# anookum_main.net
KiCad netlist of a schematic drawn in EAGLE
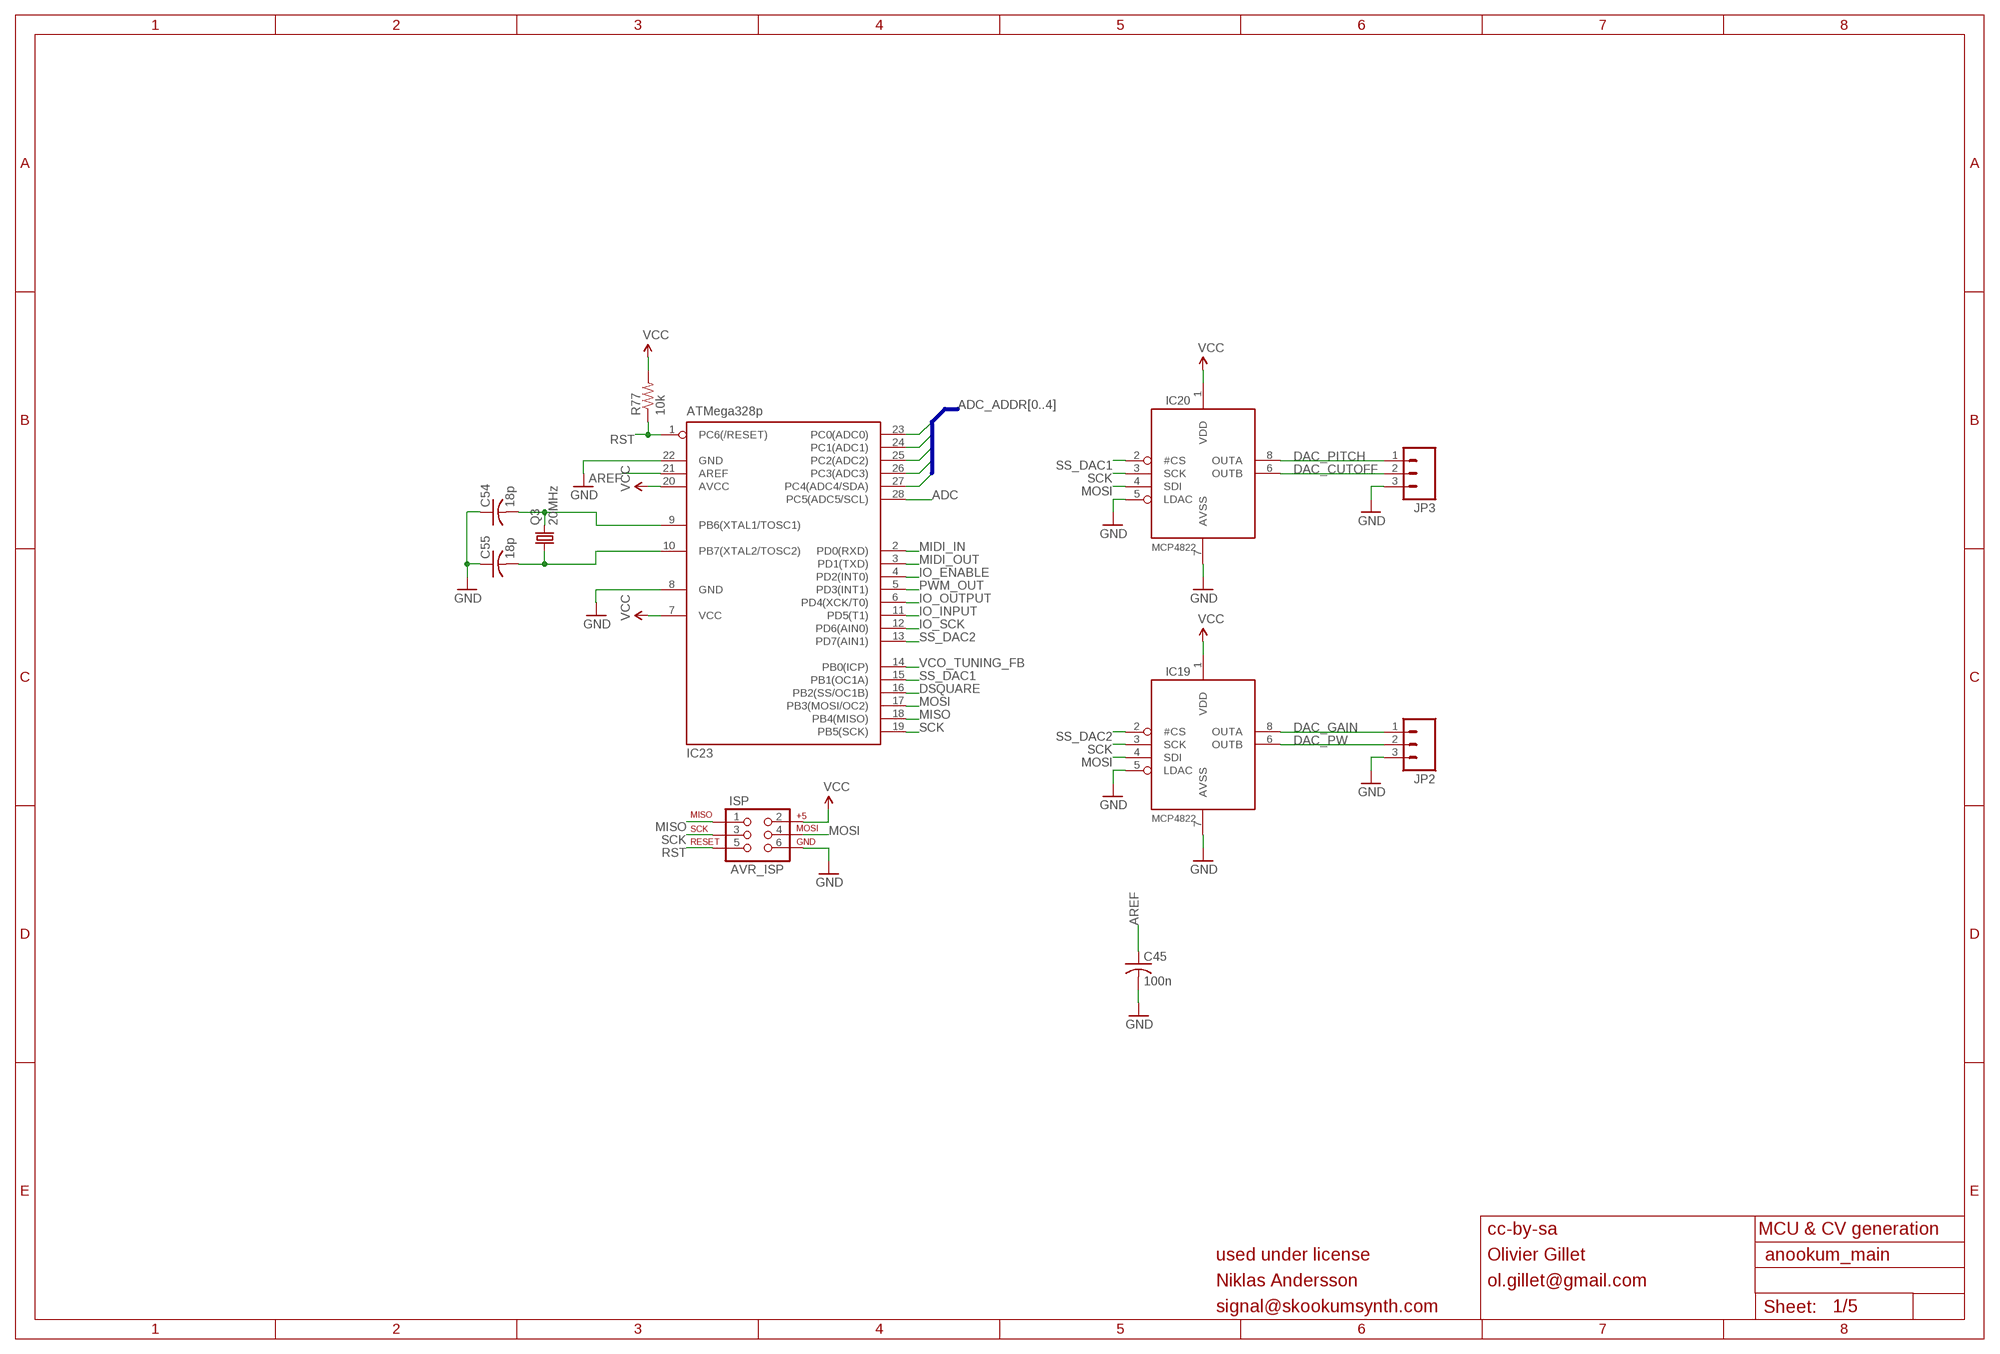
[diagram p0: schematic, sheet 1]
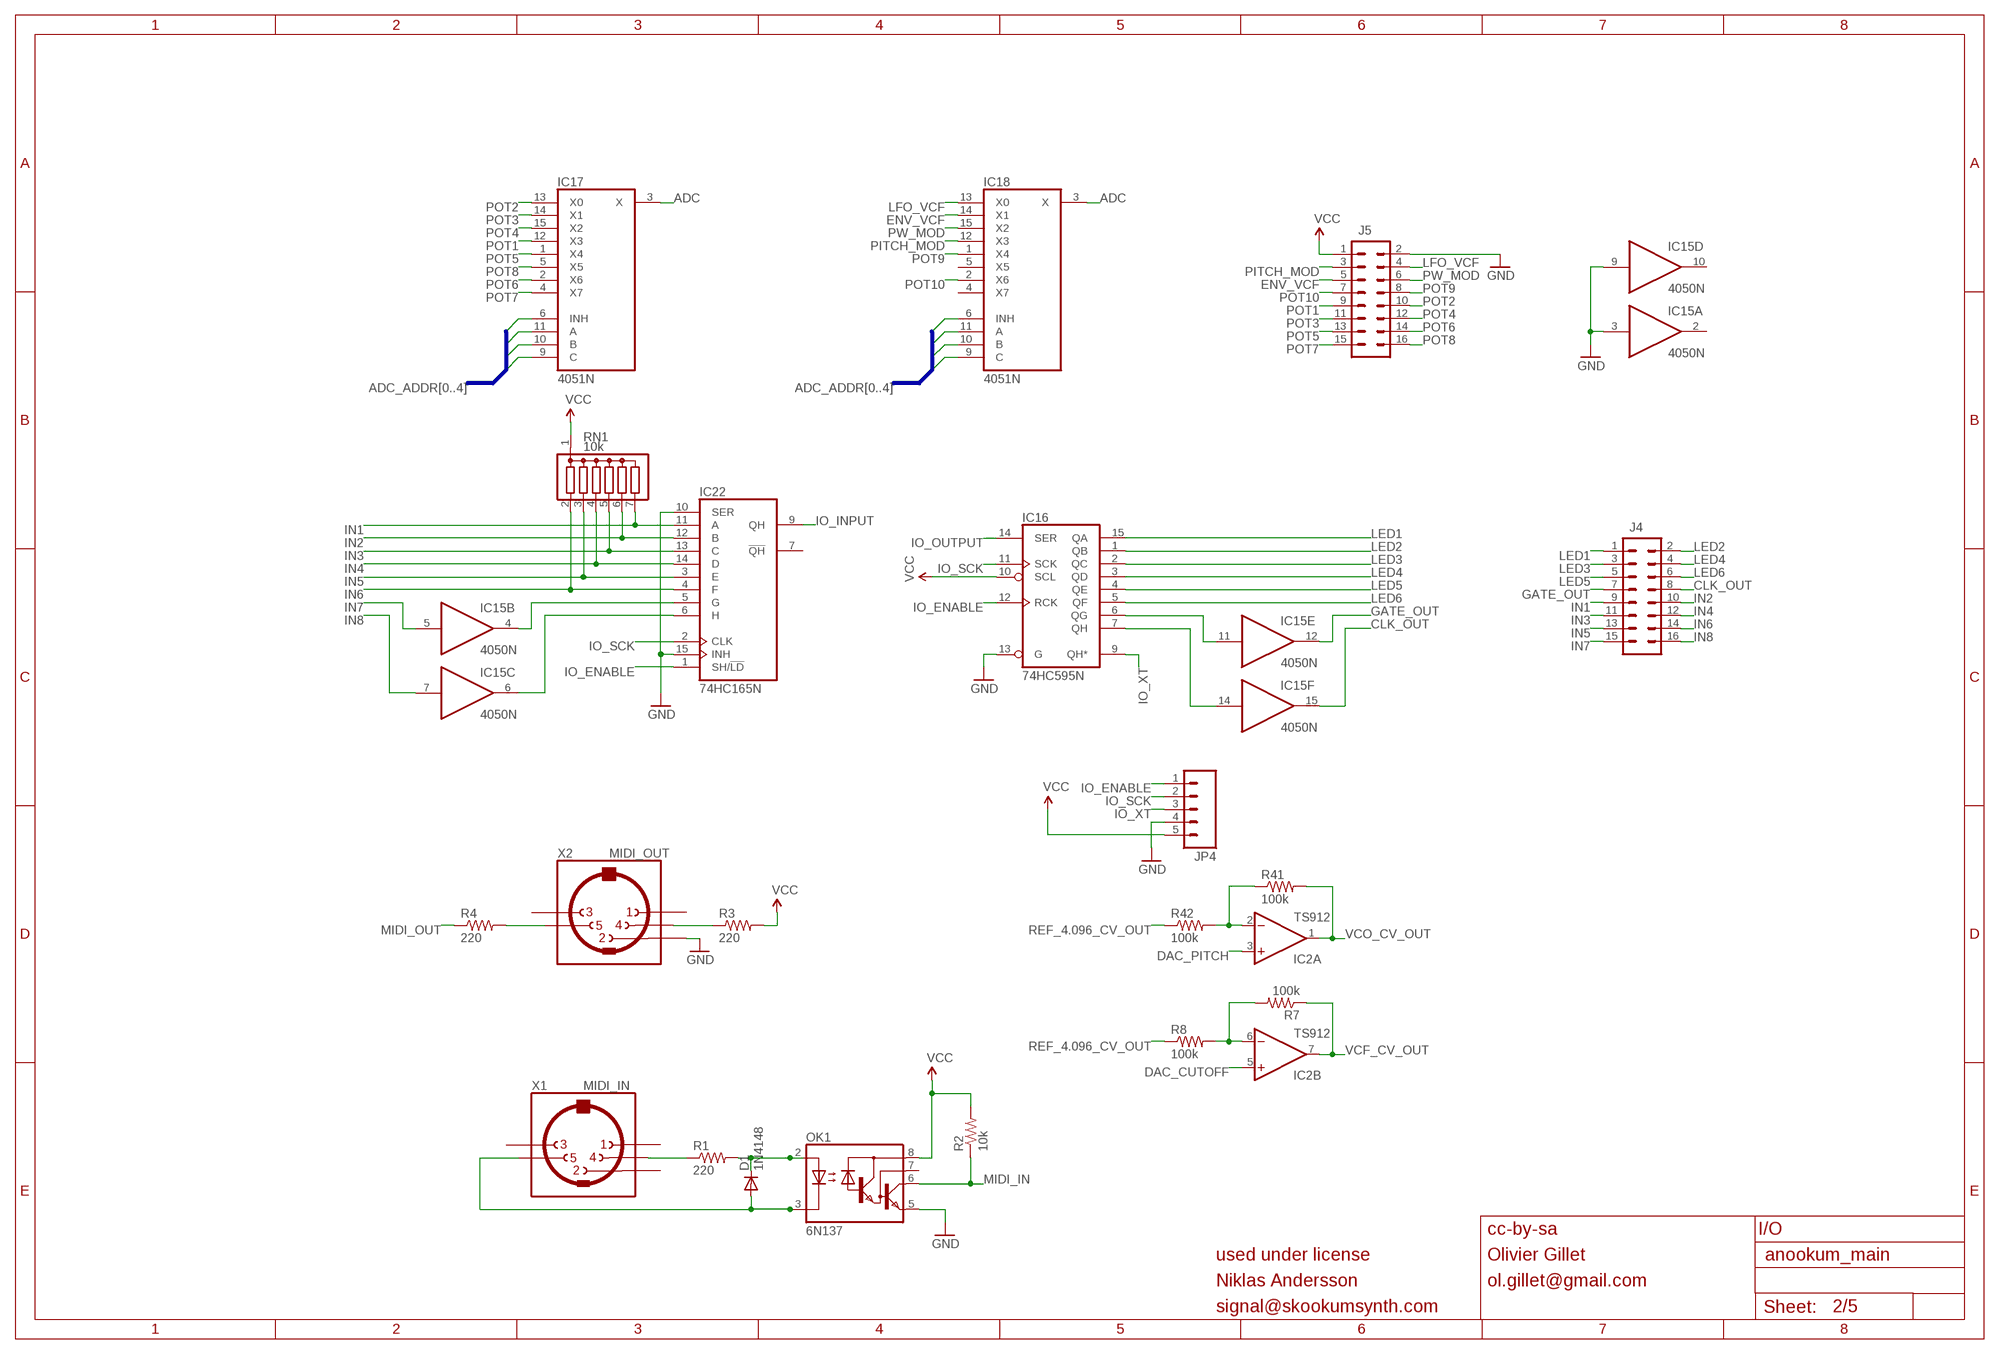
[diagram p1: schematic, sheet 2]
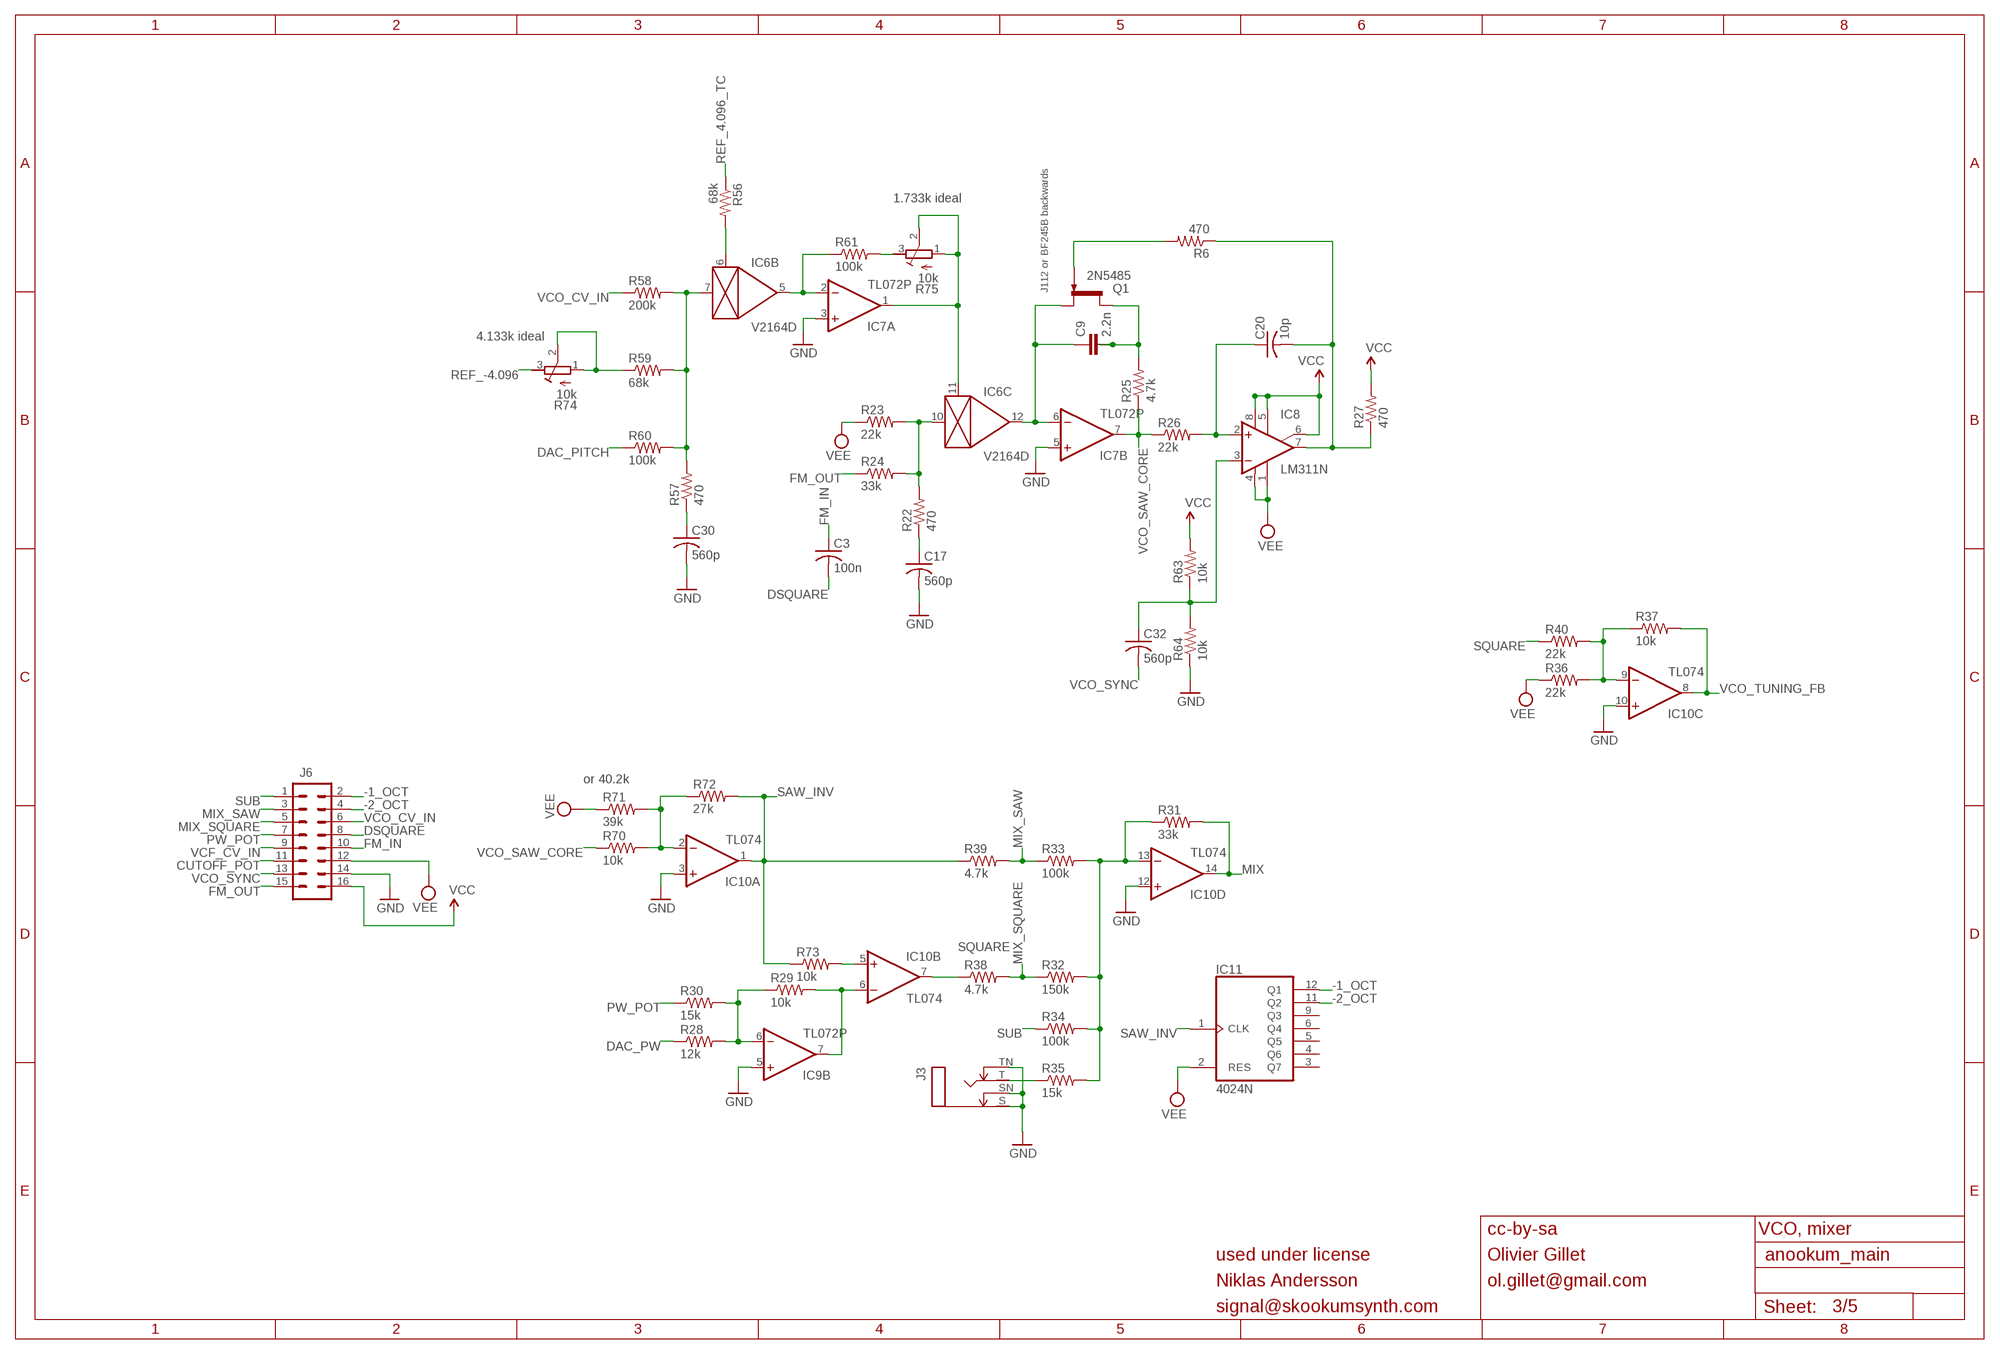
[diagram p2: schematic, sheet 3]
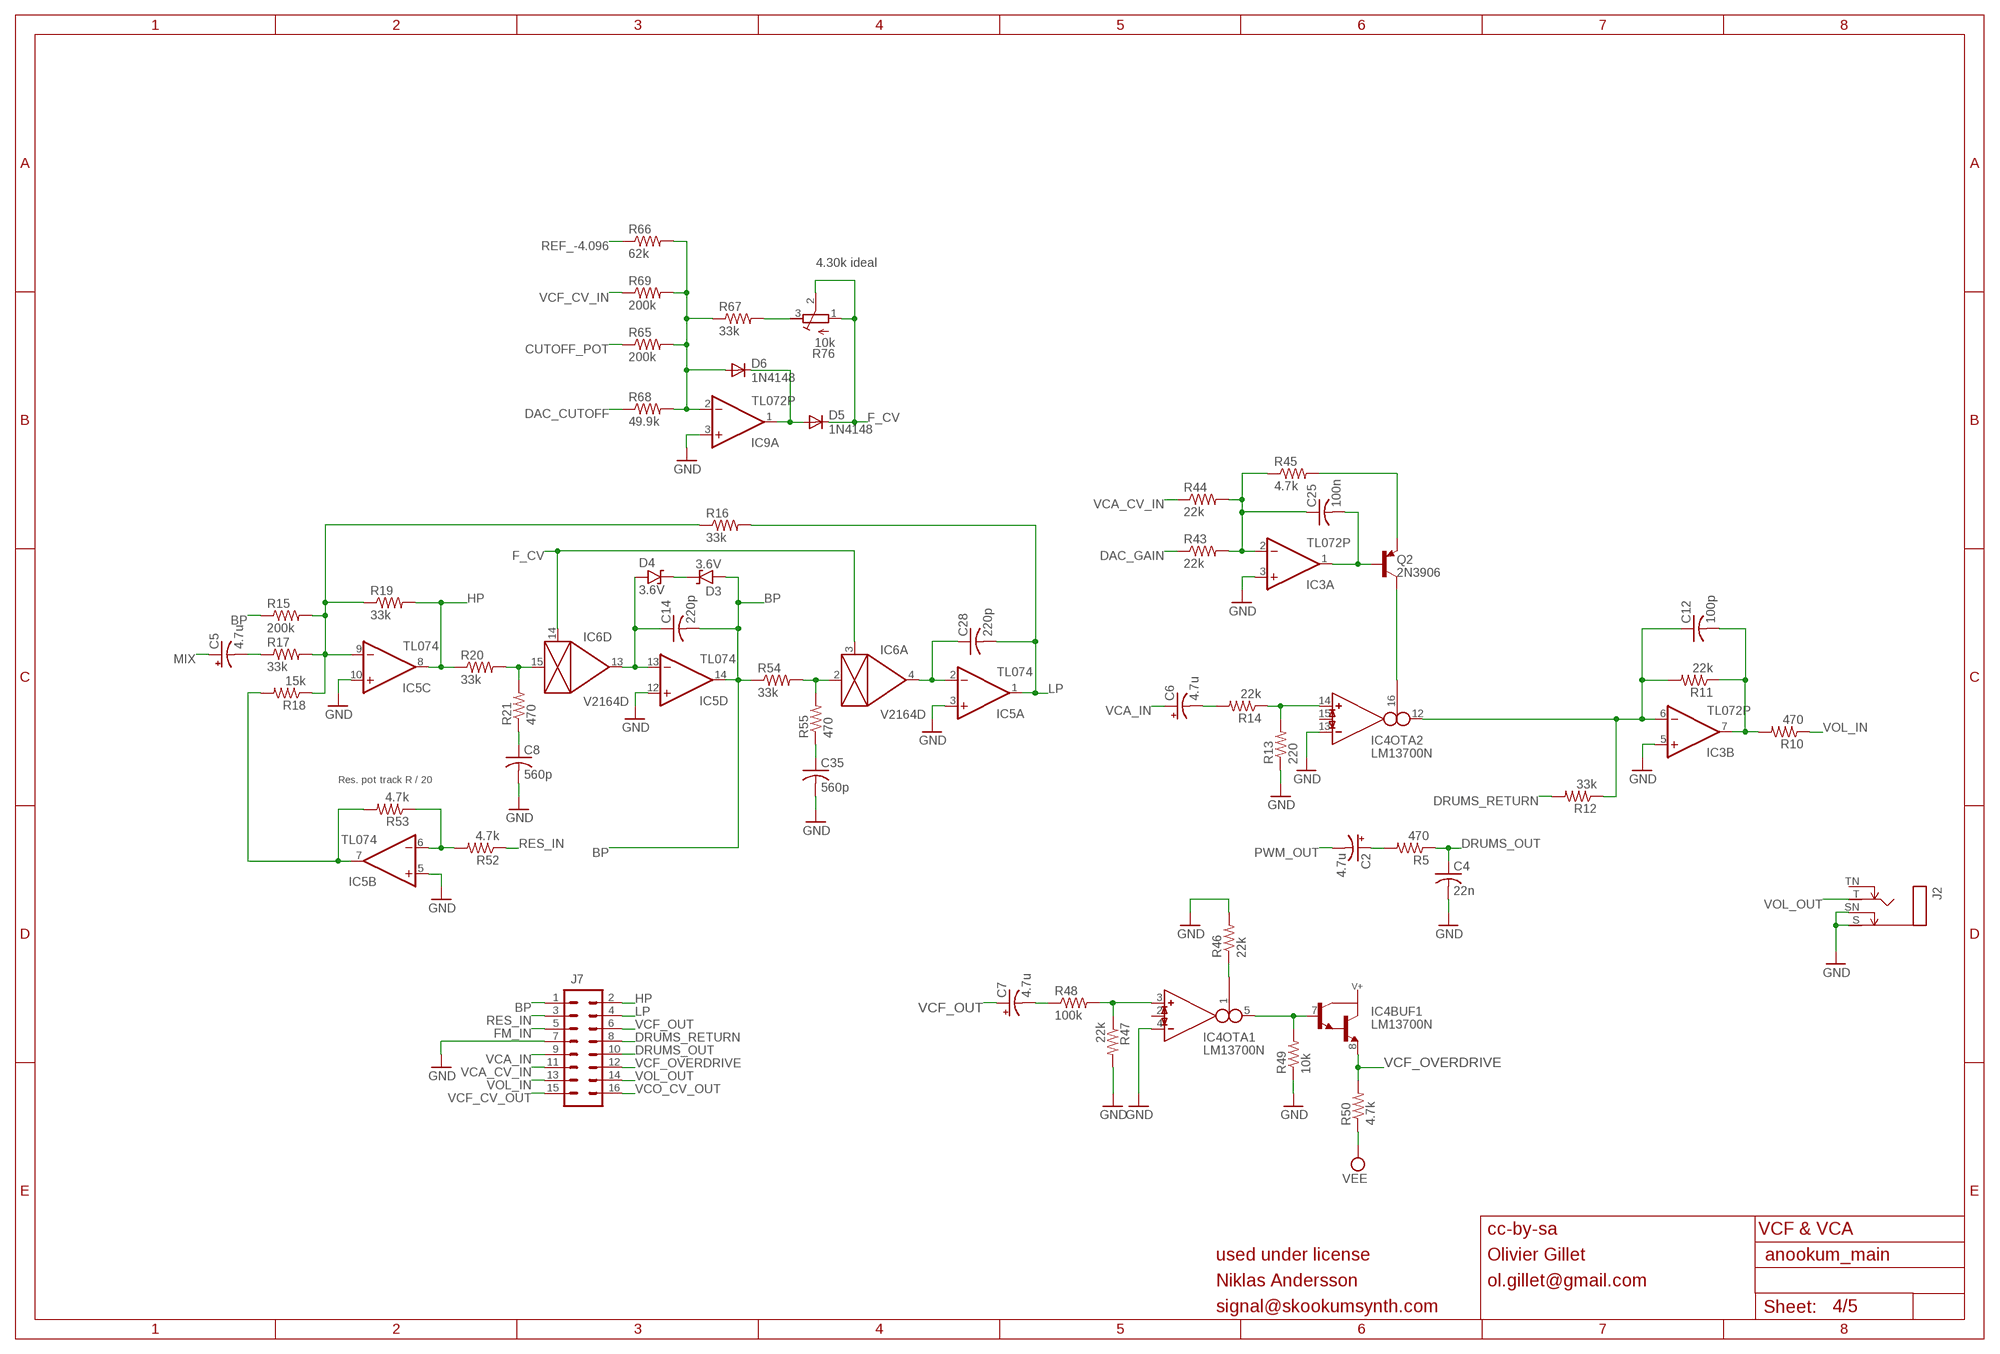
[diagram p3: schematic, sheet 4]
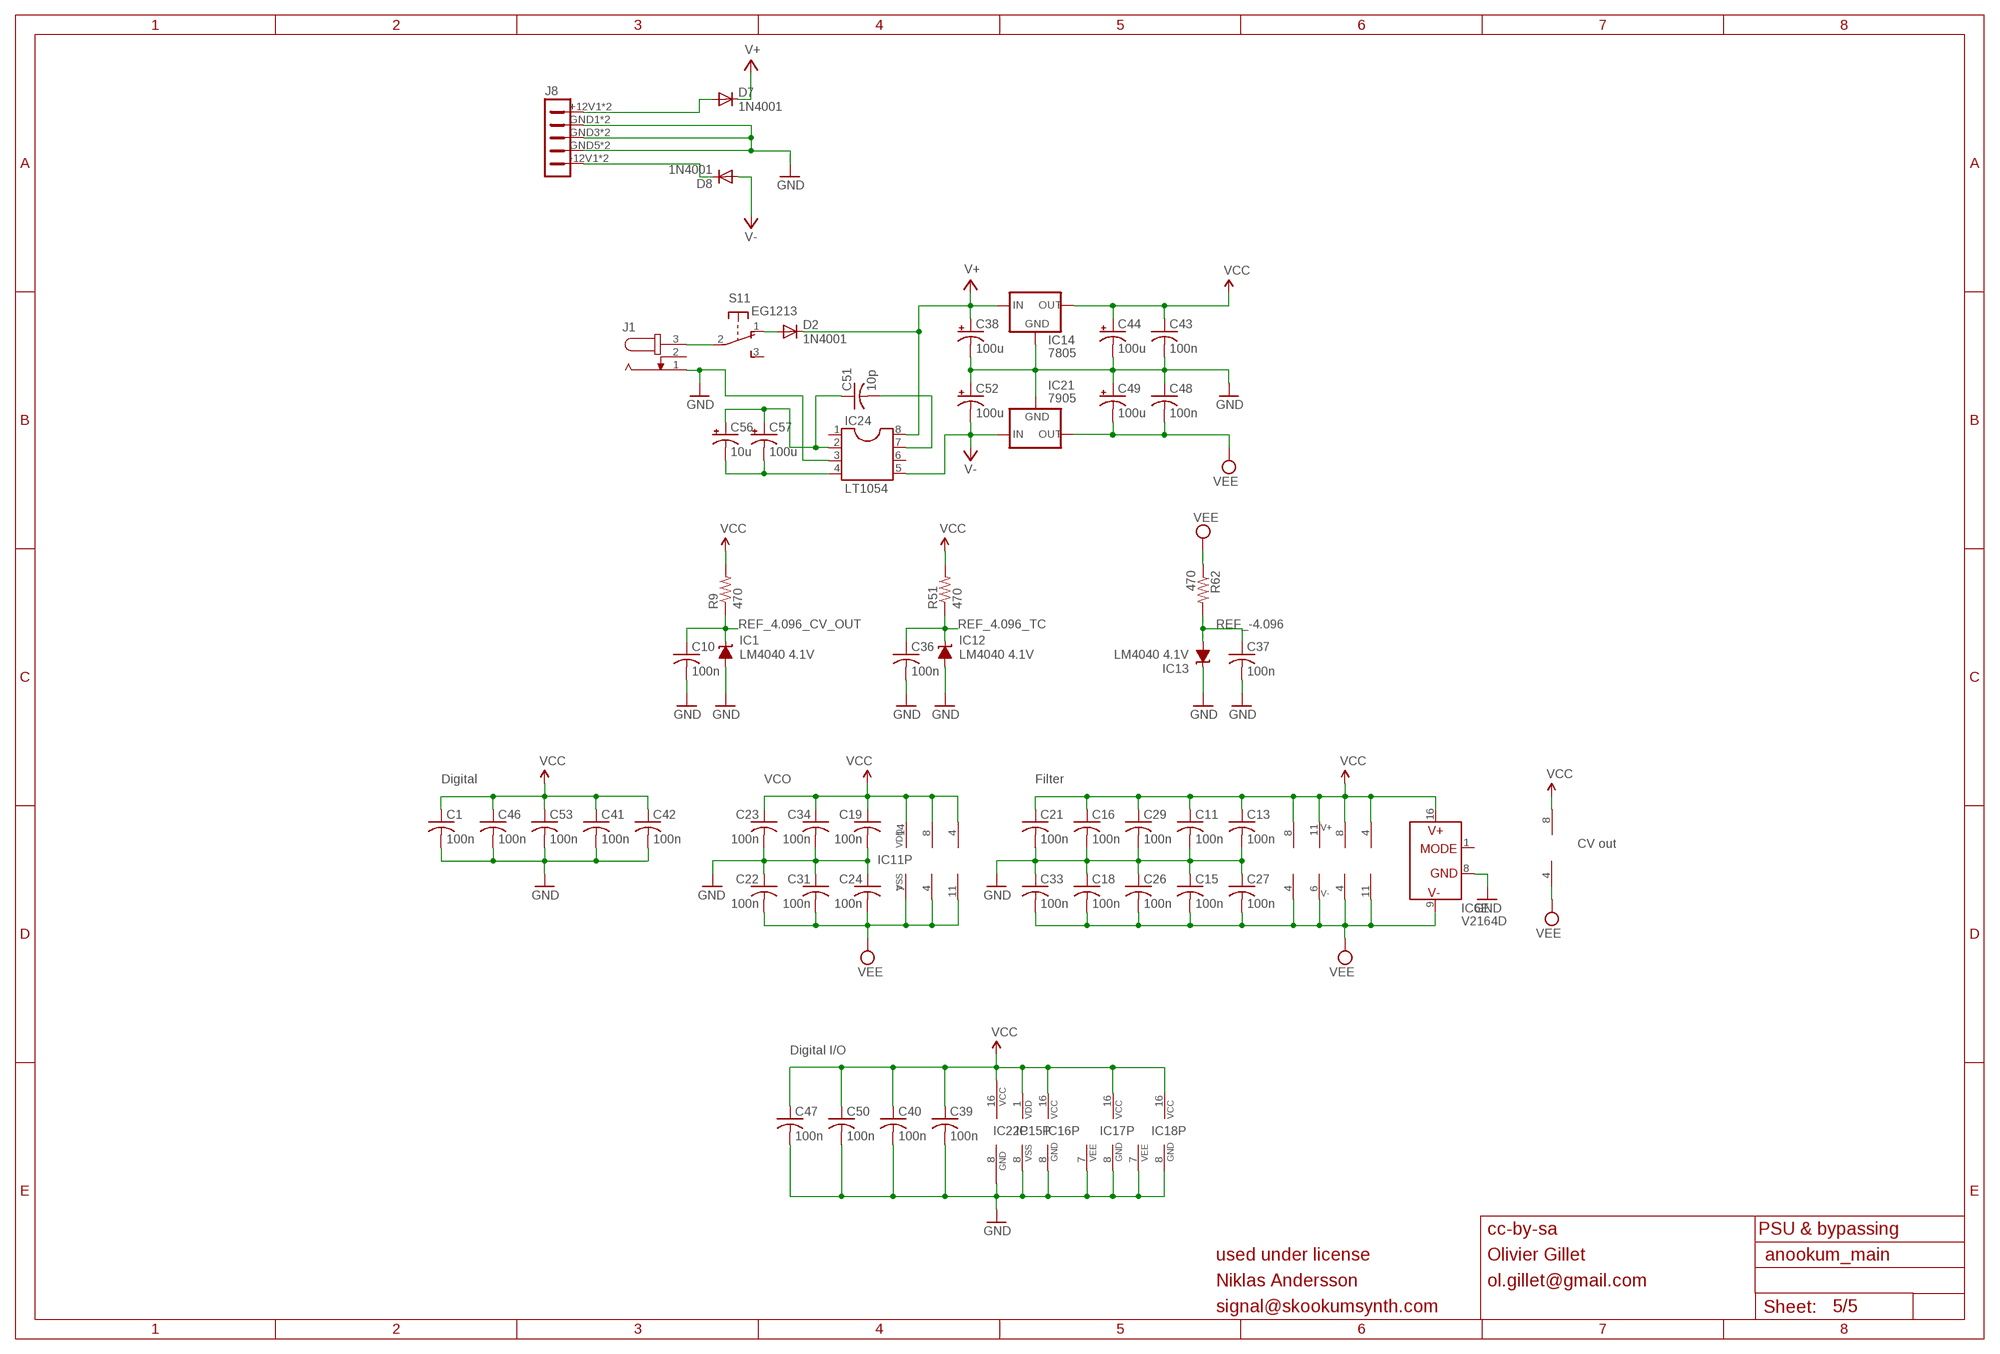
[diagram p4: schematic, sheet 5]

(export (version "E")
  (design (tool "Eeschema 10.0.6"))
  (components
    (comp (ref "C2")
      (value "4.7u")
      (footprint "eagle-import:E2,5-6")
      (libsource (lib "eagle-import") (part "CPOL-USE2.5-6"))
    )
    (comp (ref "C4")
      (value "22n")
      (footprint "eagle-import:C050-030X075")
      (libsource (lib "eagle-import") (part "C-US050-030X075"))
    )
    (comp (ref "C5")
      (value "4.7u")
      (footprint "eagle-import:E2,5-6")
      (libsource (lib "eagle-import") (part "CPOL-USE2.5-6"))
    )
    (comp (ref "C6")
      (value "4.7u")
      (footprint "eagle-import:E2,5-6")
      (libsource (lib "eagle-import") (part "CPOL-USE2.5-6"))
    )
    (comp (ref "C7")
      (value "4.7u")
      (footprint "eagle-import:E2,5-6")
      (libsource (lib "eagle-import") (part "CPOL-USE2.5-6"))
    )
    (comp (ref "C8")
      (value "560p")
      (footprint "eagle-import:C025-025X050")
      (libsource (lib "eagle-import") (part "C-US025-025X050"))
    )
    (comp (ref "C12")
      (value "100p")
      (footprint "eagle-import:C025-025X050")
      (libsource (lib "eagle-import") (part "C-US025-025X050"))
    )
    (comp (ref "C14")
      (value "220p")
      (footprint "eagle-import:C025-025X050")
      (libsource (lib "eagle-import") (part "C-US025-025X050"))
    )
    (comp (ref "C25")
      (value "100n")
      (footprint "eagle-import:C025-025X050")
      (libsource (lib "eagle-import") (part "C-US025-025X050"))
    )
    (comp (ref "C28")
      (value "220p")
      (footprint "eagle-import:C025-025X050")
      (libsource (lib "eagle-import") (part "C-US025-025X050"))
    )
    (comp (ref "C35")
      (value "560p")
      (footprint "eagle-import:C025-025X050")
      (libsource (lib "eagle-import") (part "C-US025-025X050"))
    )
    (comp (ref "D3")
      (value "3.6V")
      (footprint "eagle-import:D-5")
      (libsource (lib "eagle-import") (part "1N47XXDO35"))
    )
    (comp (ref "D4")
      (value "3.6V")
      (footprint "eagle-import:D-5")
      (libsource (lib "eagle-import") (part "1N47XXDO35"))
    )
    (comp (ref "D5")
      (value "1N4148")
      (footprint "eagle-import:D-5")
      (libsource (lib "eagle-import") (part "DIODE-D-5"))
    )
    (comp (ref "D6")
      (value "1N4148")
      (footprint "eagle-import:D-5")
      (libsource (lib "eagle-import") (part "DIODE-D-5"))
    )
    (comp (ref "IC3")
      (value "TL072P")
      (footprint "eagle-import:DIL08")
      (libsource (lib "eagle-import") (part "TL072P"))
    )
    (comp (ref "IC4")
      (value "LM13700N")
      (footprint "eagle-import:DIL16")
      (libsource (lib "eagle-import") (part "LM13700N"))
    )
    (comp (ref "IC5")
      (value "TL074")
      (footprint "eagle-import:DIL14")
      (libsource (lib "eagle-import") (part "TL084P"))
    )
    (comp (ref "IC6")
      (value "V2164D")
      (footprint "eagle-import:DIL16")
      (libsource (lib "eagle-import") (part "SSM2164P"))
    )
    (comp (ref "IC9")
      (value "TL072P")
      (footprint "eagle-import:DIL08")
      (libsource (lib "eagle-import") (part "TL072P"))
    )
    (comp (ref "J2")
      (value "MONOSWSLIM")
      (footprint "eagle-import:NRJ4HF")
      (libsource (lib "eagle-import") (part "MONOSWSLIM"))
    )
    (comp (ref "J7")
      (value "M08X2")
      (footprint "eagle-import:2X8")
      (libsource (lib "eagle-import") (part "M08X2"))
    )
    (comp (ref "Q2")
      (value "2N3906")
      (footprint "eagle-import:TO92-")
      (libsource (lib "eagle-import") (part "2N3906-"))
    )
    (comp (ref "R5")
      (value "470")
      (footprint "eagle-import:0204_7")
      (libsource (lib "eagle-import") (part "R-US_0204/7"))
    )
    (comp (ref "R10")
      (value "470")
      (footprint "eagle-import:0204_7")
      (libsource (lib "eagle-import") (part "R-US_0204/7"))
    )
    (comp (ref "R11")
      (value "22k")
      (footprint "eagle-import:0204_7")
      (libsource (lib "eagle-import") (part "R-US_0204/7"))
    )
    (comp (ref "R12")
      (value "33k")
      (footprint "eagle-import:0204_7")
      (libsource (lib "eagle-import") (part "R-US_0204/7"))
    )
    (comp (ref "R13")
      (value "220")
      (footprint "eagle-import:0204_7")
      (libsource (lib "eagle-import") (part "R-US_0204/7"))
    )
    (comp (ref "R14")
      (value "22k")
      (footprint "eagle-import:0204_7")
      (libsource (lib "eagle-import") (part "R-US_0204/7"))
    )
    (comp (ref "R15")
      (value "200k")
      (footprint "eagle-import:0204_7")
      (libsource (lib "eagle-import") (part "R-US_0204/7"))
    )
    (comp (ref "R16")
      (value "33k")
      (footprint "eagle-import:0204_7")
      (libsource (lib "eagle-import") (part "R-US_0204/7"))
    )
    (comp (ref "R17")
      (value "33k")
      (footprint "eagle-import:0204_7")
      (libsource (lib "eagle-import") (part "R-US_0204/7"))
    )
    (comp (ref "R18")
      (value "15k")
      (footprint "eagle-import:0204_7")
      (libsource (lib "eagle-import") (part "R-US_0204/7"))
    )
    (comp (ref "R19")
      (value "33k")
      (footprint "eagle-import:0204_7")
      (libsource (lib "eagle-import") (part "R-US_0204/7"))
    )
    (comp (ref "R20")
      (value "33k")
      (footprint "eagle-import:0204_7")
      (libsource (lib "eagle-import") (part "R-US_0204/7"))
    )
    (comp (ref "R21")
      (value "470")
      (footprint "eagle-import:0204_7")
      (libsource (lib "eagle-import") (part "R-US_0204/7"))
    )
    (comp (ref "R43")
      (value "22k")
      (footprint "eagle-import:0204_7")
      (libsource (lib "eagle-import") (part "R-US_0204/7"))
    )
    (comp (ref "R44")
      (value "22k")
      (footprint "eagle-import:0204_7")
      (libsource (lib "eagle-import") (part "R-US_0204/7"))
    )
    (comp (ref "R45")
      (value "4.7k")
      (footprint "eagle-import:0204_7")
      (libsource (lib "eagle-import") (part "R-US_0204/7"))
    )
    (comp (ref "R46")
      (value "22k")
      (footprint "eagle-import:0204_7")
      (libsource (lib "eagle-import") (part "R-US_0204/7"))
    )
    (comp (ref "R47")
      (value "22k")
      (footprint "eagle-import:0204_7")
      (libsource (lib "eagle-import") (part "R-US_0204/7"))
    )
    (comp (ref "R48")
      (value "100k")
      (footprint "eagle-import:0204_7")
      (libsource (lib "eagle-import") (part "R-US_0204/7"))
    )
    (comp (ref "R49")
      (value "10k")
      (footprint "eagle-import:0204_7")
      (libsource (lib "eagle-import") (part "R-US_0204/7"))
    )
    (comp (ref "R50")
      (value "4.7k")
      (footprint "eagle-import:0204_7")
      (libsource (lib "eagle-import") (part "R-US_0204/7"))
    )
    (comp (ref "R52")
      (value "4.7k")
      (footprint "eagle-import:0204_7")
      (libsource (lib "eagle-import") (part "R-US_0204/7"))
    )
    (comp (ref "R53")
      (value "4.7k")
      (footprint "eagle-import:0204_7")
      (libsource (lib "eagle-import") (part "R-US_0204/7"))
    )
    (comp (ref "R54")
      (value "33k")
      (footprint "eagle-import:0204_7")
      (libsource (lib "eagle-import") (part "R-US_0204/7"))
    )
    (comp (ref "R55")
      (value "470")
      (footprint "eagle-import:0204_7")
      (libsource (lib "eagle-import") (part "R-US_0204/7"))
    )
    (comp (ref "R65")
      (value "200k")
      (footprint "eagle-import:0204_7")
      (libsource (lib "eagle-import") (part "R-US_0204/7"))
    )
    (comp (ref "R66")
      (value "62k")
      (footprint "eagle-import:0204_7")
      (libsource (lib "eagle-import") (part "R-US_0204/7"))
    )
    (comp (ref "R67")
      (value "33k")
      (footprint "eagle-import:0204_7")
      (libsource (lib "eagle-import") (part "R-US_0204/7"))
    )
    (comp (ref "R68")
      (value "49.9k")
      (footprint "eagle-import:0204_7")
      (libsource (lib "eagle-import") (part "R-US_0204/7"))
    )
    (comp (ref "R69")
      (value "200k")
      (footprint "eagle-import:0204_7")
      (libsource (lib "eagle-import") (part "R-US_0204/7"))
    )
    (comp (ref "R76")
      (value "10k")
      (footprint "eagle-import:RTRIM3296W")
      (libsource (lib "eagle-import") (part "R-TRIMM3296W"))
    )
    (comp (ref "C45")
      (value "100n")
      (footprint "eagle-import:C025-025X050")
      (libsource (lib "eagle-import") (part "C-US025-025X050"))
    )
    (comp (ref "C54")
      (value "18p")
      (footprint "eagle-import:C025-025X050")
      (libsource (lib "eagle-import") (part "C-US025-025X050"))
    )
    (comp (ref "C55")
      (value "18p")
      (footprint "eagle-import:C025-025X050")
      (libsource (lib "eagle-import") (part "C-US025-025X050"))
    )
    (comp (ref "IC19")
      (value "MCP4822")
      (footprint "eagle-import:DIL08")
      (libsource (lib "eagle-import") (part "MCP4822"))
    )
    (comp (ref "IC20")
      (value "MCP4822")
      (footprint "eagle-import:DIL08")
      (libsource (lib "eagle-import") (part "MCP4822"))
    )
    (comp (ref "IC23")
      (value "ATMega328p")
      (footprint "eagle-import:DIL28-3")
      (libsource (lib "eagle-import") (part "MEGA8-P"))
    )
    (comp (ref "ISP")
      (value "AVR_ISP")
      (footprint "eagle-import:2X3")
      (libsource (lib "eagle-import") (part "AVR_SPI_PRG_6PTH"))
    )
    (comp (ref "JP2")
      (value "M03PTH")
      (footprint "eagle-import:1X03")
      (libsource (lib "eagle-import") (part "M03PTH"))
    )
    (comp (ref "JP3")
      (value "M03PTH")
      (footprint "eagle-import:1X03")
      (libsource (lib "eagle-import") (part "M03PTH"))
    )
    (comp (ref "Q3")
      (value "20MHz")
      (footprint "eagle-import:HC49U-V")
      (libsource (lib "eagle-import") (part "CRYSTALHC49U-V"))
    )
    (comp (ref "R77")
      (value "10k")
      (footprint "eagle-import:0204_7")
      (libsource (lib "eagle-import") (part "R-US_0204/7"))
    )
    (comp (ref "C3")
      (value "100n")
      (footprint "eagle-import:C025-025X050")
      (libsource (lib "eagle-import") (part "C-US025-025X050"))
    )
    (comp (ref "C9")
      (value "2.2n")
      (footprint "eagle-import:C2.5_5-5")
      (libsource (lib "eagle-import") (part "C-2.5-5/5"))
    )
    (comp (ref "C17")
      (value "560p")
      (footprint "eagle-import:C025-025X050")
      (libsource (lib "eagle-import") (part "C-US025-025X050"))
    )
    (comp (ref "C20")
      (value "10p")
      (footprint "eagle-import:C025-025X050")
      (libsource (lib "eagle-import") (part "C-US025-025X050"))
    )
    (comp (ref "C30")
      (value "560p")
      (footprint "eagle-import:C025-025X050")
      (libsource (lib "eagle-import") (part "C-US025-025X050"))
    )
    (comp (ref "C32")
      (value "560p")
      (footprint "eagle-import:C025-025X050")
      (libsource (lib "eagle-import") (part "C-US025-025X050"))
    )
    (comp (ref "IC7")
      (value "TL072P")
      (footprint "eagle-import:DIL08")
      (libsource (lib "eagle-import") (part "TL072P"))
    )
    (comp (ref "IC8")
      (value "LM311N")
      (footprint "eagle-import:DIL08")
      (libsource (lib "eagle-import") (part "LM311N"))
    )
    (comp (ref "IC10")
      (value "TL074")
      (footprint "eagle-import:DIL14")
      (libsource (lib "eagle-import") (part "TL084P"))
    )
    (comp (ref "IC11")
      (value "4024N")
      (footprint "eagle-import:DIL14")
      (libsource (lib "eagle-import") (part "4024N"))
    )
    (comp (ref "J3")
      (value "MONOSWSLIM")
      (footprint "eagle-import:NRJ4HF")
      (libsource (lib "eagle-import") (part "MONOSWSLIM"))
    )
    (comp (ref "J6")
      (value "M08X2")
      (footprint "eagle-import:2X8")
      (libsource (lib "eagle-import") (part "M08X2"))
    )
    (comp (ref "Q1")
      (value "2N5485")
      (footprint "eagle-import:TO92-")
      (libsource (lib "eagle-import") (part "J201"))
    )
    (comp (ref "R6")
      (value "470")
      (footprint "eagle-import:0204_7")
      (libsource (lib "eagle-import") (part "R-US_0204/7"))
    )
    (comp (ref "R22")
      (value "470")
      (footprint "eagle-import:0204_7")
      (libsource (lib "eagle-import") (part "R-US_0204/7"))
    )
    (comp (ref "R23")
      (value "22k")
      (footprint "eagle-import:0204_7")
      (libsource (lib "eagle-import") (part "R-US_0204/7"))
    )
    (comp (ref "R24")
      (value "33k")
      (footprint "eagle-import:0204_7")
      (libsource (lib "eagle-import") (part "R-US_0204/7"))
    )
    (comp (ref "R25")
      (value "4.7k")
      (footprint "eagle-import:0204_7")
      (libsource (lib "eagle-import") (part "R-US_0204/7"))
    )
    (comp (ref "R26")
      (value "22k")
      (footprint "eagle-import:0204_7")
      (libsource (lib "eagle-import") (part "R-US_0204/7"))
    )
    (comp (ref "R27")
      (value "470")
      (footprint "eagle-import:0204_7")
      (libsource (lib "eagle-import") (part "R-US_0204/7"))
    )
    (comp (ref "R28")
      (value "12k")
      (footprint "eagle-import:0204_7")
      (libsource (lib "eagle-import") (part "R-US_0204/7"))
    )
    (comp (ref "R29")
      (value "10k")
      (footprint "eagle-import:0204_7")
      (libsource (lib "eagle-import") (part "R-US_0204/7"))
    )
    (comp (ref "R30")
      (value "15k")
      (footprint "eagle-import:0204_7")
      (libsource (lib "eagle-import") (part "R-US_0204/7"))
    )
    (comp (ref "R31")
      (value "33k")
      (footprint "eagle-import:0204_7")
      (libsource (lib "eagle-import") (part "R-US_0204/7"))
    )
    (comp (ref "R32")
      (value "150k")
      (footprint "eagle-import:0204_7")
      (libsource (lib "eagle-import") (part "R-US_0204/7"))
    )
    (comp (ref "R33")
      (value "100k")
      (footprint "eagle-import:0204_7")
      (libsource (lib "eagle-import") (part "R-US_0204/7"))
    )
    (comp (ref "R34")
      (value "100k")
      (footprint "eagle-import:0204_7")
      (libsource (lib "eagle-import") (part "R-US_0204/7"))
    )
    (comp (ref "R35")
      (value "15k")
      (footprint "eagle-import:0204_7")
      (libsource (lib "eagle-import") (part "R-US_0204/7"))
    )
    (comp (ref "R36")
      (value "22k")
      (footprint "eagle-import:0204_7")
      (libsource (lib "eagle-import") (part "R-US_0204/7"))
    )
    (comp (ref "R37")
      (value "10k")
      (footprint "eagle-import:0204_7")
      (libsource (lib "eagle-import") (part "R-US_0204/7"))
    )
    (comp (ref "R38")
      (value "4.7k")
      (footprint "eagle-import:0204_7")
      (libsource (lib "eagle-import") (part "R-US_0204/7"))
    )
    (comp (ref "R39")
      (value "4.7k")
      (footprint "eagle-import:0204_7")
      (libsource (lib "eagle-import") (part "R-US_0204/7"))
    )
    (comp (ref "R40")
      (value "22k")
      (footprint "eagle-import:0204_7")
      (libsource (lib "eagle-import") (part "R-US_0204/7"))
    )
    (comp (ref "R56")
      (value "68k")
      (footprint "eagle-import:0204_7")
      (libsource (lib "eagle-import") (part "R-US_0204/7"))
    )
    (comp (ref "R57")
      (value "470")
      (footprint "eagle-import:0204_7")
      (libsource (lib "eagle-import") (part "R-US_0204/7"))
    )
    (comp (ref "R58")
      (value "200k")
      (footprint "eagle-import:0204_7")
      (libsource (lib "eagle-import") (part "R-US_0204/7"))
    )
    (comp (ref "R59")
      (value "68k")
      (footprint "eagle-import:0204_7")
      (libsource (lib "eagle-import") (part "R-US_0204/7"))
    )
    (comp (ref "R60")
      (value "100k")
      (footprint "eagle-import:0204_7")
      (libsource (lib "eagle-import") (part "R-US_0204/7"))
    )
    (comp (ref "R61")
      (value "100k")
      (footprint "eagle-import:0204_7")
      (libsource (lib "eagle-import") (part "R-US_0204/7"))
    )
    (comp (ref "R63")
      (value "10k")
      (footprint "eagle-import:0204_7")
      (libsource (lib "eagle-import") (part "R-US_0204/7"))
    )
    (comp (ref "R64")
      (value "10k")
      (footprint "eagle-import:0204_7")
      (libsource (lib "eagle-import") (part "R-US_0204/7"))
    )
    (comp (ref "R70")
      (value "10k")
      (footprint "eagle-import:0204_7")
      (libsource (lib "eagle-import") (part "R-US_0204/7"))
    )
    (comp (ref "R71")
      (value "39k")
      (footprint "eagle-import:0204_7")
      (libsource (lib "eagle-import") (part "R-US_0204/7"))
    )
    (comp (ref "R72")
      (value "27k")
      (footprint "eagle-import:0204_7")
      (libsource (lib "eagle-import") (part "R-US_0204/7"))
    )
    (comp (ref "R73")
      (value "10k")
      (footprint "eagle-import:0204_7")
      (libsource (lib "eagle-import") (part "R-US_0204/7"))
    )
    (comp (ref "R74")
      (value "10k")
      (footprint "eagle-import:RTRIM3296W")
      (libsource (lib "eagle-import") (part "R-TRIMM3296W"))
    )
    (comp (ref "R75")
      (value "10k")
      (footprint "eagle-import:RTRIM3296W")
      (libsource (lib "eagle-import") (part "R-TRIMM3296W"))
    )
    (comp (ref "D1")
      (value "1N4148")
      (footprint "eagle-import:D-5")
      (libsource (lib "eagle-import") (part "DIODE-D-5"))
    )
    (comp (ref "IC2")
      (value "TS912")
      (footprint "eagle-import:DIL08")
      (libsource (lib "eagle-import") (part "TL072P"))
    )
    (comp (ref "IC15")
      (value "4050N")
      (footprint "eagle-import:DIL16")
      (libsource (lib "eagle-import") (part "4050N"))
    )
    (comp (ref "IC16")
      (value "74HC595N")
      (footprint "eagle-import:DIL16")
      (libsource (lib "eagle-import") (part "74595NHC"))
    )
    (comp (ref "IC17")
      (value "4051N")
      (footprint "eagle-import:DIL16")
      (libsource (lib "eagle-import") (part "4051N"))
    )
    (comp (ref "IC18")
      (value "4051N")
      (footprint "eagle-import:DIL16")
      (libsource (lib "eagle-import") (part "4051N"))
    )
    (comp (ref "IC22")
      (value "74HC165N")
      (footprint "eagle-import:DIL16")
      (libsource (lib "eagle-import") (part "74165NLS"))
    )
    (comp (ref "J4")
      (value "M08X2")
      (footprint "eagle-import:2X8")
      (libsource (lib "eagle-import") (part "M08X2"))
    )
    (comp (ref "J5")
      (value "M08X2")
      (footprint "eagle-import:2X8")
      (libsource (lib "eagle-import") (part "M08X2"))
    )
    (comp (ref "JP4")
      (value "M05PTH")
      (footprint "eagle-import:1X05")
      (libsource (lib "eagle-import") (part "M05PTH"))
    )
    (comp (ref "OK1")
      (value "6N137")
      (footprint "eagle-import:DIL08")
      (libsource (lib "eagle-import") (part "6N138"))
    )
    (comp (ref "R1")
      (value "220")
      (footprint "eagle-import:0204_7")
      (libsource (lib "eagle-import") (part "R-US_0204/7"))
    )
    (comp (ref "R2")
      (value "10k")
      (footprint "eagle-import:0204_7")
      (libsource (lib "eagle-import") (part "R-US_0204/7"))
    )
    (comp (ref "R3")
      (value "220")
      (footprint "eagle-import:0204_7")
      (libsource (lib "eagle-import") (part "R-US_0204/7"))
    )
    (comp (ref "R4")
      (value "220")
      (footprint "eagle-import:0204_7")
      (libsource (lib "eagle-import") (part "R-US_0204/7"))
    )
    (comp (ref "R7")
      (value "100k")
      (footprint "eagle-import:0204_7")
      (libsource (lib "eagle-import") (part "R-US_0204/7"))
    )
    (comp (ref "R8")
      (value "100k")
      (footprint "eagle-import:0204_7")
      (libsource (lib "eagle-import") (part "R-US_0204/7"))
    )
    (comp (ref "R41")
      (value "100k")
      (footprint "eagle-import:0204_7")
      (libsource (lib "eagle-import") (part "R-US_0204/7"))
    )
    (comp (ref "R42")
      (value "100k")
      (footprint "eagle-import:0204_7")
      (libsource (lib "eagle-import") (part "R-US_0204/7"))
    )
    (comp (ref "RN1")
      (value "10k")
      (footprint "eagle-import:SIL7")
      (libsource (lib "eagle-import") (part "G06R"))
    )
    (comp (ref "X1")
      (value "MIDI_IN")
      (footprint "eagle-import:SDS-50J")
      (libsource (lib "eagle-import") (part "CONN_MIDI_F"))
    )
    (comp (ref "X2")
      (value "MIDI_OUT")
      (footprint "eagle-import:SDS-50J")
      (libsource (lib "eagle-import") (part "CONN_MIDI_F"))
    )
    (comp (ref "C1")
      (value "100n")
      (footprint "eagle-import:C025-025X050")
      (libsource (lib "eagle-import") (part "C-US025-025X050"))
    )
    (comp (ref "C10")
      (value "100n")
      (footprint "eagle-import:C025-025X050")
      (libsource (lib "eagle-import") (part "C-US025-025X050"))
    )
    (comp (ref "C11")
      (value "100n")
      (footprint "eagle-import:C025-025X050")
      (libsource (lib "eagle-import") (part "C-US025-025X050"))
    )
    (comp (ref "C13")
      (value "100n")
      (footprint "eagle-import:C025-025X050")
      (libsource (lib "eagle-import") (part "C-US025-025X050"))
    )
    (comp (ref "C15")
      (value "100n")
      (footprint "eagle-import:C025-025X050")
      (libsource (lib "eagle-import") (part "C-US025-025X050"))
    )
    (comp (ref "C16")
      (value "100n")
      (footprint "eagle-import:C025-025X050")
      (libsource (lib "eagle-import") (part "C-US025-025X050"))
    )
    (comp (ref "C18")
      (value "100n")
      (footprint "eagle-import:C025-025X050")
      (libsource (lib "eagle-import") (part "C-US025-025X050"))
    )
    (comp (ref "C19")
      (value "100n")
      (footprint "eagle-import:C025-025X050")
      (libsource (lib "eagle-import") (part "C-US025-025X050"))
    )
    (comp (ref "C21")
      (value "100n")
      (footprint "eagle-import:C025-025X050")
      (libsource (lib "eagle-import") (part "C-US025-025X050"))
    )
    (comp (ref "C22")
      (value "100n")
      (footprint "eagle-import:C025-025X050")
      (libsource (lib "eagle-import") (part "C-US025-025X050"))
    )
    (comp (ref "C23")
      (value "100n")
      (footprint "eagle-import:C025-025X050")
      (libsource (lib "eagle-import") (part "C-US025-025X050"))
    )
    (comp (ref "C24")
      (value "100n")
      (footprint "eagle-import:C025-025X050")
      (libsource (lib "eagle-import") (part "C-US025-025X050"))
    )
    (comp (ref "C26")
      (value "100n")
      (footprint "eagle-import:C025-025X050")
      (libsource (lib "eagle-import") (part "C-US025-025X050"))
    )
    (comp (ref "C27")
      (value "100n")
      (footprint "eagle-import:C025-025X050")
      (libsource (lib "eagle-import") (part "C-US025-025X050"))
    )
    (comp (ref "C29")
      (value "100n")
      (footprint "eagle-import:C025-025X050")
      (libsource (lib "eagle-import") (part "C-US025-025X050"))
    )
    (comp (ref "C31")
      (value "100n")
      (footprint "eagle-import:C025-025X050")
      (libsource (lib "eagle-import") (part "C-US025-025X050"))
    )
    (comp (ref "C33")
      (value "100n")
      (footprint "eagle-import:C025-025X050")
      (libsource (lib "eagle-import") (part "C-US025-025X050"))
    )
    (comp (ref "C34")
      (value "100n")
      (footprint "eagle-import:C025-025X050")
      (libsource (lib "eagle-import") (part "C-US025-025X050"))
    )
    (comp (ref "C36")
      (value "100n")
      (footprint "eagle-import:C025-025X050")
      (libsource (lib "eagle-import") (part "C-US025-025X050"))
    )
    (comp (ref "C37")
      (value "100n")
      (footprint "eagle-import:C025-025X050")
      (libsource (lib "eagle-import") (part "C-US025-025X050"))
    )
    (comp (ref "C38")
      (value "100u")
      (footprint "eagle-import:E2,5-7")
      (libsource (lib "eagle-import") (part "CPOL-USE2.5-7"))
    )
    (comp (ref "C39")
      (value "100n")
      (footprint "eagle-import:C025-025X050")
      (libsource (lib "eagle-import") (part "C-US025-025X050"))
    )
    (comp (ref "C40")
      (value "100n")
      (footprint "eagle-import:C025-025X050")
      (libsource (lib "eagle-import") (part "C-US025-025X050"))
    )
    (comp (ref "C41")
      (value "100n")
      (footprint "eagle-import:C025-025X050")
      (libsource (lib "eagle-import") (part "C-US025-025X050"))
    )
    (comp (ref "C42")
      (value "100n")
      (footprint "eagle-import:C025-025X050")
      (libsource (lib "eagle-import") (part "C-US025-025X050"))
    )
    (comp (ref "C43")
      (value "100n")
      (footprint "eagle-import:C025-025X050")
      (libsource (lib "eagle-import") (part "C-US025-025X050"))
    )
    (comp (ref "C44")
      (value "100u")
      (footprint "eagle-import:E2,5-7")
      (libsource (lib "eagle-import") (part "CPOL-USE2.5-7"))
    )
    (comp (ref "C46")
      (value "100n")
      (footprint "eagle-import:C025-025X050")
      (libsource (lib "eagle-import") (part "C-US025-025X050"))
    )
    (comp (ref "C47")
      (value "100n")
      (footprint "eagle-import:C025-025X050")
      (libsource (lib "eagle-import") (part "C-US025-025X050"))
    )
    (comp (ref "C48")
      (value "100n")
      (footprint "eagle-import:C025-025X050")
      (libsource (lib "eagle-import") (part "C-US025-025X050"))
    )
    (comp (ref "C49")
      (value "100u")
      (footprint "eagle-import:E2,5-7")
      (libsource (lib "eagle-import") (part "CPOL-USE2.5-7"))
    )
    (comp (ref "C50")
      (value "100n")
      (footprint "eagle-import:C025-025X050")
      (libsource (lib "eagle-import") (part "C-US025-025X050"))
    )
    (comp (ref "C51")
      (value "10p")
      (footprint "eagle-import:C025-025X050")
      (libsource (lib "eagle-import") (part "C-US025-025X050"))
    )
    (comp (ref "C52")
      (value "100u")
      (footprint "eagle-import:E2,5-7")
      (libsource (lib "eagle-import") (part "CPOL-USE2.5-7"))
    )
    (comp (ref "C53")
      (value "100n")
      (footprint "eagle-import:C025-025X050")
      (libsource (lib "eagle-import") (part "C-US025-025X050"))
    )
    (comp (ref "C56")
      (value "10u")
      (footprint "eagle-import:E2,5-5")
      (libsource (lib "eagle-import") (part "CPOL-USE2.5-5"))
    )
    (comp (ref "C57")
      (value "100u")
      (footprint "eagle-import:E2,5-6")
      (libsource (lib "eagle-import") (part "CPOL-USE2.5-6"))
    )
    (comp (ref "D2")
      (value "1N4001")
      (footprint "eagle-import:DO41-10")
      (libsource (lib "eagle-import") (part "1N4004"))
    )
    (comp (ref "D7")
      (value "1N4001")
      (footprint "eagle-import:DO41-10")
      (libsource (lib "eagle-import") (part "1N4004"))
    )
    (comp (ref "D8")
      (value "1N4001")
      (footprint "eagle-import:DO41-10")
      (libsource (lib "eagle-import") (part "1N4004"))
    )
    (comp (ref "IC1")
      (value "LM4040 4.1V")
      (footprint "eagle-import:LP_O-PBCY-W3")
      (libsource (lib "eagle-import") (part "LM4041LPC12"))
    )
    (comp (ref "IC12")
      (value "LM4040 4.1V")
      (footprint "eagle-import:LP_O-PBCY-W3")
      (libsource (lib "eagle-import") (part "LM4041LPC12"))
    )
    (comp (ref "IC13")
      (value "LM4040 4.1V")
      (footprint "eagle-import:LP_O-PBCY-W3")
      (libsource (lib "eagle-import") (part "LM4041LPC12"))
    )
    (comp (ref "IC14")
      (value "7805")
      (footprint "eagle-import:78XXS")
      (libsource (lib "eagle-import") (part "78XXS"))
    )
    (comp (ref "IC21")
      (value "7905")
      (footprint "eagle-import:79XXS")
      (libsource (lib "eagle-import") (part "79XXS"))
    )
    (comp (ref "IC24")
      (value "LT1054")
      (footprint "eagle-import:DIL08")
      (libsource (lib "eagle-import") (part "DIL8"))
    )
    (comp (ref "J1")
      (value "JACK-PLUG2")
      (footprint "eagle-import:SPC4078_BIG_HOLES")
      (libsource (lib "eagle-import") (part "JACK-PLUG2"))
    )
    (comp (ref "J8")
      (value "HDR_POWER_10_VERT")
      (footprint "eagle-import:HDR_POWER_10")
      (libsource (lib "eagle-import") (part "HDR_POWER_10_VERT"))
    )
    (comp (ref "R9")
      (value "470")
      (footprint "eagle-import:0204_7")
      (libsource (lib "eagle-import") (part "resistor_R-US_0204/7"))
    )
    (comp (ref "R51")
      (value "470")
      (footprint "eagle-import:0204_7")
      (libsource (lib "eagle-import") (part "resistor_R-US_0204/7"))
    )
    (comp (ref "R62")
      (value "470")
      (footprint "eagle-import:0204_7")
      (libsource (lib "eagle-import") (part "resistor_R-US_0204/7"))
    )
    (comp (ref "S1")
      (value "EG1213")
      (footprint "eagle-import:EG1213")
      (libsource (lib "eagle-import") (part "EG1213"))
    )
  )
  (nets
    (net (code "1") (name "-1_OCT") (class "Default")
      (node (ref "IC11") (pin "12") (pinfunction "Q1_12") (pintype "output"))
      (node (ref "J6") (pin "2") (pinfunction "2_2") (pintype "passive"))
    )
    (net (code "2") (name "-2_OCT") (class "Default")
      (node (ref "IC11") (pin "11") (pinfunction "Q2_11") (pintype "output"))
      (node (ref "J6") (pin "4") (pinfunction "4_4") (pintype "passive"))
    )
    (net (code "5") (name "ADC") (class "Default")
      (node (ref "IC17") (pin "3") (pinfunction "X_3") (pintype "bidirectional"))
      (node (ref "IC18") (pin "3") (pinfunction "X_3") (pintype "bidirectional"))
      (node (ref "IC23") (pin "28") (pinfunction "PC5(ADC5/SCL)_28") (pintype "bidirectional"))
    )
    (net (code "6") (name "ADC_ADDR0") (class "Default")
      (node (ref "IC17") (pin "11") (pinfunction "A_11") (pintype "input"))
      (node (ref "IC18") (pin "11") (pinfunction "A_11") (pintype "input"))
      (node (ref "IC23") (pin "25") (pinfunction "PC2(ADC2)_25") (pintype "bidirectional"))
    )
    (net (code "7") (name "ADC_ADDR1") (class "Default")
      (node (ref "IC17") (pin "10") (pinfunction "B_10") (pintype "input"))
      (node (ref "IC18") (pin "10") (pinfunction "B_10") (pintype "input"))
      (node (ref "IC23") (pin "24") (pinfunction "PC1(ADC1)_24") (pintype "bidirectional"))
    )
    (net (code "8") (name "ADC_ADDR2") (class "Default")
      (node (ref "IC17") (pin "9") (pinfunction "C_9") (pintype "input"))
      (node (ref "IC18") (pin "9") (pinfunction "C_9") (pintype "input"))
      (node (ref "IC23") (pin "23") (pinfunction "PC0(ADC0)_23") (pintype "bidirectional"))
    )
    (net (code "9") (name "ADC_ADDR3") (class "Default")
      (node (ref "IC17") (pin "6") (pinfunction "INH_6") (pintype "input"))
      (node (ref "IC23") (pin "26") (pinfunction "PC3(ADC3)_26") (pintype "bidirectional"))
    )
    (net (code "10") (name "ADC_ADDR4") (class "Default")
      (node (ref "IC18") (pin "6") (pinfunction "INH_6") (pintype "input"))
      (node (ref "IC23") (pin "27") (pinfunction "PC4(ADC4/SDA)_27") (pintype "bidirectional"))
    )
    (net (code "11") (name "AREF") (class "Default")
      (node (ref "C45") (pin "1") (pinfunction "1_1") (pintype "passive"))
      (node (ref "IC23") (pin "21") (pinfunction "AREF_21") (pintype "passive"))
    )
    (net (code "12") (name "BP") (class "Default")
      (node (ref "C14") (pin "2") (pinfunction "2_2") (pintype "passive"))
      (node (ref "D3") (pin "A") (pinfunction "A_A") (pintype "passive"))
      (node (ref "IC5") (pin "14") (pinfunction "OUT_14") (pintype "output"))
      (node (ref "J7") (pin "1") (pinfunction "1_1") (pintype "passive"))
      (node (ref "R15") (pin "1") (pinfunction "1_1") (pintype "passive"))
      (node (ref "R54") (pin "1") (pinfunction "1_1") (pintype "passive"))
    )
    (net (code "13") (name "CLK_OUT") (class "Default")
      (node (ref "IC15") (pin "15") (pinfunction "O_15") (pintype "output"))
      (node (ref "J4") (pin "8") (pinfunction "8_8") (pintype "passive"))
    )
    (net (code "14") (name "CUTOFF_POT") (class "Default")
      (node (ref "J6") (pin "11") (pinfunction "11_11") (pintype "passive"))
      (node (ref "R65") (pin "1") (pinfunction "1_1") (pintype "passive"))
    )
    (net (code "15") (name "DAC_CUTOFF") (class "Default")
      (node (ref "IC2") (pin "5") (pinfunction "+IN_5") (pintype "input"))
      (node (ref "IC20") (pin "6") (pinfunction "OUTB_6") (pintype "output"))
      (node (ref "JP3") (pin "2") (pinfunction "2_2") (pintype "passive"))
      (node (ref "R68") (pin "1") (pinfunction "1_1") (pintype "passive"))
    )
    (net (code "16") (name "DAC_GAIN") (class "Default")
      (node (ref "IC19") (pin "8") (pinfunction "OUTA_8") (pintype "output"))
      (node (ref "JP2") (pin "1") (pinfunction "1_1") (pintype "passive"))
      (node (ref "R43") (pin "1") (pinfunction "1_1") (pintype "passive"))
    )
    (net (code "17") (name "DAC_PITCH") (class "Default")
      (node (ref "IC2") (pin "3") (pinfunction "+IN_3") (pintype "input"))
      (node (ref "IC20") (pin "8") (pinfunction "OUTA_8") (pintype "output"))
      (node (ref "JP3") (pin "1") (pinfunction "1_1") (pintype "passive"))
      (node (ref "R60") (pin "1") (pinfunction "1_1") (pintype "passive"))
    )
    (net (code "18") (name "DAC_PW") (class "Default")
      (node (ref "IC19") (pin "6") (pinfunction "OUTB_6") (pintype "output"))
      (node (ref "JP2") (pin "2") (pinfunction "2_2") (pintype "passive"))
      (node (ref "R28") (pin "1") (pinfunction "1_1") (pintype "passive"))
    )
    (net (code "19") (name "DRUMS_OUT") (class "Default")
      (node (ref "C4") (pin "1") (pinfunction "1_1") (pintype "passive"))
      (node (ref "J7") (pin "10") (pinfunction "10_10") (pintype "passive"))
      (node (ref "R5") (pin "1") (pinfunction "1_1") (pintype "passive"))
    )
    (net (code "20") (name "DRUMS_RETURN") (class "Default")
      (node (ref "J7") (pin "8") (pinfunction "8_8") (pintype "passive"))
      (node (ref "R12") (pin "2") (pinfunction "2_2") (pintype "passive"))
    )
    (net (code "21") (name "DSQUARE") (class "Default")
      (node (ref "C3") (pin "2") (pinfunction "2_2") (pintype "passive"))
      (node (ref "IC23") (pin "16") (pinfunction "PB2(SS/OC1B)_16") (pintype "bidirectional"))
      (node (ref "J6") (pin "8") (pinfunction "8_8") (pintype "passive"))
    )
    (net (code "22") (name "ENV_VCF") (class "Default")
      (node (ref "IC18") (pin "14") (pinfunction "X1_14") (pintype "bidirectional"))
      (node (ref "J5") (pin "5") (pinfunction "5_5") (pintype "passive"))
    )
    (net (code "23") (name "FM_IN") (class "Default")
      (node (ref "C3") (pin "1") (pinfunction "1_1") (pintype "passive"))
      (node (ref "J6") (pin "10") (pinfunction "10_10") (pintype "passive"))
      (node (ref "J7") (pin "5") (pinfunction "5_5") (pintype "passive"))
    )
    (net (code "24") (name "FM_OUT") (class "Default")
      (node (ref "J6") (pin "15") (pinfunction "15_15") (pintype "passive"))
      (node (ref "R24") (pin "1") (pinfunction "1_1") (pintype "passive"))
    )
    (net (code "25") (name "F_CV") (class "Default")
      (node (ref "D5") (pin "C") (pinfunction "C_C") (pintype "passive"))
      (node (ref "IC6") (pin "14") (pinfunction "CTRL_14") (pintype "input"))
      (node (ref "IC6") (pin "3") (pinfunction "CTRL_3") (pintype "input"))
      (node (ref "R76") (pin "1") (pinfunction "E_1") (pintype "passive"))
      (node (ref "R76") (pin "2") (pinfunction "S_2") (pintype "passive"))
    )
    (net (code "26") (name "GATE_OUT") (class "Default")
      (node (ref "IC15") (pin "12") (pinfunction "O_12") (pintype "output"))
      (node (ref "J4") (pin "7") (pinfunction "7_7") (pintype "passive"))
    )
    (net (code "27") (name "GND") (class "Default")
      (node (ref "C1") (pin "2") (pinfunction "2_2") (pintype "passive"))
      (node (ref "C10") (pin "2") (pinfunction "2_2") (pintype "passive"))
      (node (ref "C11") (pin "2") (pinfunction "2_2") (pintype "passive"))
      (node (ref "C13") (pin "2") (pinfunction "2_2") (pintype "passive"))
      (node (ref "C15") (pin "1") (pinfunction "1_1") (pintype "passive"))
      (node (ref "C16") (pin "2") (pinfunction "2_2") (pintype "passive"))
      (node (ref "C17") (pin "2") (pinfunction "2_2") (pintype "passive"))
      (node (ref "C18") (pin "1") (pinfunction "1_1") (pintype "passive"))
      (node (ref "C19") (pin "2") (pinfunction "2_2") (pintype "passive"))
      (node (ref "C21") (pin "2") (pinfunction "2_2") (pintype "passive"))
      (node (ref "C22") (pin "1") (pinfunction "1_1") (pintype "passive"))
      (node (ref "C23") (pin "2") (pinfunction "2_2") (pintype "passive"))
      (node (ref "C24") (pin "1") (pinfunction "1_1") (pintype "passive"))
      (node (ref "C26") (pin "1") (pinfunction "1_1") (pintype "passive"))
      (node (ref "C27") (pin "1") (pinfunction "1_1") (pintype "passive"))
      (node (ref "C29") (pin "2") (pinfunction "2_2") (pintype "passive"))
      (node (ref "C30") (pin "2") (pinfunction "2_2") (pintype "passive"))
      (node (ref "C31") (pin "1") (pinfunction "1_1") (pintype "passive"))
      (node (ref "C33") (pin "1") (pinfunction "1_1") (pintype "passive"))
      (node (ref "C34") (pin "2") (pinfunction "2_2") (pintype "passive"))
      (node (ref "C35") (pin "2") (pinfunction "2_2") (pintype "passive"))
      (node (ref "C36") (pin "2") (pinfunction "2_2") (pintype "passive"))
      (node (ref "C37") (pin "2") (pinfunction "2_2") (pintype "passive"))
      (node (ref "C38") (pin "-") (pinfunction "-_-") (pintype "passive"))
      (node (ref "C39") (pin "2") (pinfunction "2_2") (pintype "passive"))
      (node (ref "C4") (pin "2") (pinfunction "2_2") (pintype "passive"))
      (node (ref "C40") (pin "2") (pinfunction "2_2") (pintype "passive"))
      (node (ref "C41") (pin "2") (pinfunction "2_2") (pintype "passive"))
      (node (ref "C42") (pin "2") (pinfunction "2_2") (pintype "passive"))
      (node (ref "C43") (pin "2") (pinfunction "2_2") (pintype "passive"))
      (node (ref "C44") (pin "-") (pinfunction "-_-") (pintype "passive"))
      (node (ref "C45") (pin "2") (pinfunction "2_2") (pintype "passive"))
      (node (ref "C46") (pin "2") (pinfunction "2_2") (pintype "passive"))
      (node (ref "C47") (pin "2") (pinfunction "2_2") (pintype "passive"))
      (node (ref "C48") (pin "1") (pinfunction "1_1") (pintype "passive"))
      (node (ref "C49") (pin "+") (pinfunction "+_+") (pintype "passive"))
      (node (ref "C50") (pin "2") (pinfunction "2_2") (pintype "passive"))
      (node (ref "C52") (pin "+") (pinfunction "+_+") (pintype "passive"))
      (node (ref "C53") (pin "2") (pinfunction "2_2") (pintype "passive"))
      (node (ref "C54") (pin "1") (pinfunction "1_1") (pintype "passive"))
      (node (ref "C55") (pin "1") (pinfunction "1_1") (pintype "passive"))
      (node (ref "C8") (pin "2") (pinfunction "2_2") (pintype "passive"))
      (node (ref "IC1") (pin "3") (pinfunction "A_3") (pintype "passive"))
      (node (ref "IC10") (pin "10") (pinfunction "+IN_10") (pintype "input"))
      (node (ref "IC10") (pin "12") (pinfunction "+IN_12") (pintype "input"))
      (node (ref "IC10") (pin "3") (pinfunction "+IN_3") (pintype "input"))
      (node (ref "IC12") (pin "3") (pinfunction "A_3") (pintype "passive"))
      (node (ref "IC13") (pin "2") (pinfunction "C_2") (pintype "passive"))
      (node (ref "IC14") (pin "GND") (pinfunction "GND_GND") (pintype "input"))
      (node (ref "IC15") (pin "3") (pinfunction "I_3") (pintype "input"))
      (node (ref "IC15") (pin "8") (pinfunction "VSS_8") (pintype "power_in"))
      (node (ref "IC15") (pin "9") (pinfunction "I_9") (pintype "input"))
      (node (ref "IC16") (pin "13") (pinfunction "G_13") (pintype "input"))
      (node (ref "IC16") (pin "8") (pinfunction "GND_8") (pintype "power_in"))
      (node (ref "IC17") (pin "7") (pinfunction "VEE_7") (pintype "power_in"))
      (node (ref "IC17") (pin "8") (pinfunction "GND_8") (pintype "power_in"))
      (node (ref "IC18") (pin "7") (pinfunction "VEE_7") (pintype "power_in"))
      (node (ref "IC18") (pin "8") (pinfunction "GND_8") (pintype "power_in"))
      (node (ref "IC19") (pin "5") (pinfunction "LDAC_5") (pintype "input"))
      (node (ref "IC19") (pin "7") (pinfunction "AVSS_7") (pintype "power_in"))
      (node (ref "IC20") (pin "5") (pinfunction "LDAC_5") (pintype "input"))
      (node (ref "IC20") (pin "7") (pinfunction "AVSS_7") (pintype "power_in"))
      (node (ref "IC21") (pin "GND") (pinfunction "GND_GND") (pintype "input"))
      (node (ref "IC22") (pin "10") (pinfunction "SER_10") (pintype "input"))
      (node (ref "IC22") (pin "15") (pinfunction "INH_15") (pintype "input"))
      (node (ref "IC22") (pin "8") (pinfunction "GND_8") (pintype "power_in"))
      (node (ref "IC23") (pin "22") (pinfunction "GND_22") (pintype "power_in"))
      (node (ref "IC23") (pin "8") (pinfunction "GND_8") (pintype "power_in"))
      (node (ref "IC24") (pin "3") (pinfunction "3_3") (pintype "passive"))
      (node (ref "IC3") (pin "3") (pinfunction "+IN_3") (pintype "input"))
      (node (ref "IC3") (pin "5") (pinfunction "+IN_5") (pintype "input"))
      (node (ref "IC4") (pin "13") (pinfunction "IN_N_13") (pintype "input"))
      (node (ref "IC4") (pin "4") (pinfunction "IN_N_4") (pintype "input"))
      (node (ref "IC5") (pin "10") (pinfunction "+IN_10") (pintype "input"))
      (node (ref "IC5") (pin "12") (pinfunction "+IN_12") (pintype "input"))
      (node (ref "IC5") (pin "3") (pinfunction "+IN_3") (pintype "input"))
      (node (ref "IC5") (pin "5") (pinfunction "+IN_5") (pintype "input"))
      (node (ref "IC6") (pin "8") (pinfunction "GND_8") (pintype "power_in"))
      (node (ref "IC7") (pin "3") (pinfunction "+IN_3") (pintype "input"))
      (node (ref "IC7") (pin "5") (pinfunction "+IN_5") (pintype "input"))
      (node (ref "IC9") (pin "3") (pinfunction "+IN_3") (pintype "input"))
      (node (ref "IC9") (pin "5") (pinfunction "+IN_5") (pintype "input"))
      (node (ref "ISP") (pin "6") (pinfunction "6_6") (pintype "passive"))
      (node (ref "J1") (pin "1") (pinfunction "1_1") (pintype "passive"))
      (node (ref "J2") (pin "S") (pinfunction "S_S") (pintype "passive"))
      (node (ref "J2") (pin "SN") (pinfunction "SN_SN") (pintype "passive"))
      (node (ref "J3") (pin "S") (pinfunction "S_S") (pintype "passive"))
      (node (ref "J3") (pin "SN") (pinfunction "SN_SN") (pintype "passive"))
      (node (ref "J3") (pin "TN") (pinfunction "TN_TN") (pintype "passive"))
      (node (ref "J5") (pin "2") (pinfunction "2_2") (pintype "passive"))
      (node (ref "J6") (pin "14") (pinfunction "14_14") (pintype "passive"))
      (node (ref "J7") (pin "7") (pinfunction "7_7") (pintype "passive"))
      (node (ref "J8") (pin "GND1") (pinfunction "2_GND1") (pintype "passive"))
      (node (ref "J8") (pin "GND2") (pinfunction "2_GND2") (pintype "passive"))
      (node (ref "J8") (pin "GND3") (pinfunction "3_GND3") (pintype "passive"))
      (node (ref "J8") (pin "GND4") (pinfunction "3_GND4") (pintype "passive"))
      (node (ref "J8") (pin "GND5") (pinfunction "4_GND5") (pintype "passive"))
      (node (ref "J8") (pin "GND6") (pinfunction "4_GND6") (pintype "passive"))
      (node (ref "JP2") (pin "3") (pinfunction "3_3") (pintype "passive"))
      (node (ref "JP3") (pin "3") (pinfunction "3_3") (pintype "passive"))
      (node (ref "JP4") (pin "4") (pinfunction "4_4") (pintype "passive"))
      (node (ref "OK1") (pin "5") (pinfunction "GND_5") (pintype "passive"))
      (node (ref "R13") (pin "1") (pinfunction "1_1") (pintype "passive"))
      (node (ref "R46") (pin "2") (pinfunction "2_2") (pintype "passive"))
      (node (ref "R47") (pin "2") (pinfunction "2_2") (pintype "passive"))
      (node (ref "R49") (pin "1") (pinfunction "1_1") (pintype "passive"))
      (node (ref "R64") (pin "1") (pinfunction "1_1") (pintype "passive"))
      (node (ref "X2") (pin "2") (pinfunction "2_2") (pintype "passive"))
    )
    (net (code "28") (name "HP") (class "Default")
      (node (ref "IC5") (pin "8") (pinfunction "OUT_8") (pintype "output"))
      (node (ref "J7") (pin "2") (pinfunction "2_2") (pintype "passive"))
      (node (ref "R19") (pin "2") (pinfunction "2_2") (pintype "passive"))
      (node (ref "R20") (pin "1") (pinfunction "1_1") (pintype "passive"))
    )
    (net (code "29") (name "IN1") (class "Default")
      (node (ref "IC22") (pin "11") (pinfunction "A_11") (pintype "input"))
      (node (ref "J4") (pin "9") (pinfunction "9_9") (pintype "passive"))
      (node (ref "RN1") (pin "7") (pinfunction "7_7") (pintype "passive"))
    )
    (net (code "30") (name "IN2") (class "Default")
      (node (ref "IC22") (pin "12") (pinfunction "B_12") (pintype "input"))
      (node (ref "J4") (pin "10") (pinfunction "10_10") (pintype "passive"))
      (node (ref "RN1") (pin "6") (pinfunction "6_6") (pintype "passive"))
    )
    (net (code "31") (name "IN3") (class "Default")
      (node (ref "IC22") (pin "13") (pinfunction "C_13") (pintype "input"))
      (node (ref "J4") (pin "11") (pinfunction "11_11") (pintype "passive"))
      (node (ref "RN1") (pin "5") (pinfunction "5_5") (pintype "passive"))
    )
    (net (code "32") (name "IN4") (class "Default")
      (node (ref "IC22") (pin "14") (pinfunction "D_14") (pintype "input"))
      (node (ref "J4") (pin "12") (pinfunction "12_12") (pintype "passive"))
      (node (ref "RN1") (pin "4") (pinfunction "4_4") (pintype "passive"))
    )
    (net (code "33") (name "IN5") (class "Default")
      (node (ref "IC22") (pin "3") (pinfunction "E_3") (pintype "input"))
      (node (ref "J4") (pin "13") (pinfunction "13_13") (pintype "passive"))
      (node (ref "RN1") (pin "3") (pinfunction "3_3") (pintype "passive"))
    )
    (net (code "34") (name "IN6") (class "Default")
      (node (ref "IC22") (pin "4") (pinfunction "F_4") (pintype "input"))
      (node (ref "J4") (pin "14") (pinfunction "14_14") (pintype "passive"))
      (node (ref "RN1") (pin "2") (pinfunction "2_2") (pintype "passive"))
    )
    (net (code "35") (name "IN7") (class "Default")
      (node (ref "IC15") (pin "5") (pinfunction "I_5") (pintype "input"))
      (node (ref "J4") (pin "15") (pinfunction "15_15") (pintype "passive"))
    )
    (net (code "36") (name "IN8") (class "Default")
      (node (ref "IC15") (pin "7") (pinfunction "I_7") (pintype "input"))
      (node (ref "J4") (pin "16") (pinfunction "16_16") (pintype "passive"))
    )
    (net (code "37") (name "IO_ENABLE") (class "Default")
      (node (ref "IC16") (pin "12") (pinfunction "RCK_12") (pintype "input"))
      (node (ref "IC22") (pin "1") (pinfunction "SH/~{LD}_1") (pintype "input"))
      (node (ref "IC23") (pin "4") (pinfunction "PD2(INT0)_4") (pintype "bidirectional"))
      (node (ref "JP4") (pin "1") (pinfunction "1_1") (pintype "passive"))
    )
    (net (code "38") (name "IO_INPUT") (class "Default")
      (node (ref "IC22") (pin "9") (pinfunction "QH_9") (pintype "output"))
      (node (ref "IC23") (pin "11") (pinfunction "PD5(T1)_11") (pintype "bidirectional"))
    )
    (net (code "39") (name "IO_OUTPUT") (class "Default")
      (node (ref "IC16") (pin "14") (pinfunction "SER_14") (pintype "input"))
      (node (ref "IC23") (pin "6") (pinfunction "PD4(XCK/T0)_6") (pintype "bidirectional"))
    )
    (net (code "40") (name "IO_SCK") (class "Default")
      (node (ref "IC16") (pin "11") (pinfunction "SCK_11") (pintype "input"))
      (node (ref "IC22") (pin "2") (pinfunction "CLK_2") (pintype "input"))
      (node (ref "IC23") (pin "12") (pinfunction "PD6(AIN0)_12") (pintype "bidirectional"))
      (node (ref "JP4") (pin "2") (pinfunction "2_2") (pintype "passive"))
    )
    (net (code "41") (name "IO_XT") (class "Default")
      (node (ref "IC16") (pin "9") (pinfunction "QH*_9") (pintype "tri_state"))
      (node (ref "JP4") (pin "3") (pinfunction "3_3") (pintype "passive"))
    )
    (net (code "42") (name "LED1") (class "Default")
      (node (ref "IC16") (pin "15") (pinfunction "QA_15") (pintype "tri_state"))
      (node (ref "J4") (pin "1") (pinfunction "1_1") (pintype "passive"))
    )
    (net (code "43") (name "LED2") (class "Default")
      (node (ref "IC16") (pin "1") (pinfunction "QB_1") (pintype "tri_state"))
      (node (ref "J4") (pin "2") (pinfunction "2_2") (pintype "passive"))
    )
    (net (code "44") (name "LED3") (class "Default")
      (node (ref "IC16") (pin "2") (pinfunction "QC_2") (pintype "tri_state"))
      (node (ref "J4") (pin "3") (pinfunction "3_3") (pintype "passive"))
    )
    (net (code "45") (name "LED4") (class "Default")
      (node (ref "IC16") (pin "3") (pinfunction "QD_3") (pintype "tri_state"))
      (node (ref "J4") (pin "4") (pinfunction "4_4") (pintype "passive"))
    )
    (net (code "46") (name "LED5") (class "Default")
      (node (ref "IC16") (pin "4") (pinfunction "QE_4") (pintype "tri_state"))
      (node (ref "J4") (pin "5") (pinfunction "5_5") (pintype "passive"))
    )
    (net (code "47") (name "LED6") (class "Default")
      (node (ref "IC16") (pin "5") (pinfunction "QF_5") (pintype "tri_state"))
      (node (ref "J4") (pin "6") (pinfunction "6_6") (pintype "passive"))
    )
    (net (code "48") (name "LFO_VCF") (class "Default")
      (node (ref "IC18") (pin "13") (pinfunction "X0_13") (pintype "bidirectional"))
      (node (ref "J5") (pin "4") (pinfunction "4_4") (pintype "passive"))
    )
    (net (code "49") (name "LP") (class "Default")
      (node (ref "C28") (pin "2") (pinfunction "2_2") (pintype "passive"))
      (node (ref "IC5") (pin "1") (pinfunction "OUT_1") (pintype "output"))
      (node (ref "J7") (pin "4") (pinfunction "4_4") (pintype "passive"))
      (node (ref "R16") (pin "2") (pinfunction "2_2") (pintype "passive"))
    )
    (net (code "50") (name "MIDI_IN") (class "Default")
      (node (ref "IC23") (pin "2") (pinfunction "PD0(RXD)_2") (pintype "bidirectional"))
      (node (ref "OK1") (pin "6") (pinfunction "VO_6") (pintype "passive"))
      (node (ref "R2") (pin "1") (pinfunction "1_1") (pintype "passive"))
    )
    (net (code "51") (name "MIDI_OUT") (class "Default")
      (node (ref "IC23") (pin "3") (pinfunction "PD1(TXD)_3") (pintype "bidirectional"))
      (node (ref "R4") (pin "1") (pinfunction "1_1") (pintype "passive"))
    )
    (net (code "52") (name "MISO") (class "Default")
      (node (ref "IC23") (pin "18") (pinfunction "PB4(MISO)_18") (pintype "bidirectional"))
      (node (ref "ISP") (pin "1") (pinfunction "1_1") (pintype "passive"))
    )
    (net (code "53") (name "MIX") (class "Default")
      (node (ref "C5") (pin "+") (pinfunction "+_+") (pintype "passive"))
      (node (ref "IC10") (pin "14") (pinfunction "OUT_14") (pintype "output"))
      (node (ref "R31") (pin "2") (pinfunction "2_2") (pintype "passive"))
    )
    (net (code "54") (name "MIX_SAW") (class "Default")
      (node (ref "J6") (pin "3") (pinfunction "3_3") (pintype "passive"))
      (node (ref "R33") (pin "1") (pinfunction "1_1") (pintype "passive"))
      (node (ref "R39") (pin "2") (pinfunction "2_2") (pintype "passive"))
    )
    (net (code "55") (name "MIX_SQUARE") (class "Default")
      (node (ref "J6") (pin "5") (pinfunction "5_5") (pintype "passive"))
      (node (ref "R32") (pin "1") (pinfunction "1_1") (pintype "passive"))
      (node (ref "R38") (pin "2") (pinfunction "2_2") (pintype "passive"))
    )
    (net (code "56") (name "MOSI") (class "Default")
      (node (ref "IC19") (pin "4") (pinfunction "SDI_4") (pintype "input"))
      (node (ref "IC20") (pin "4") (pinfunction "SDI_4") (pintype "input"))
      (node (ref "IC23") (pin "17") (pinfunction "PB3(MOSI/OC2)_17") (pintype "bidirectional"))
      (node (ref "ISP") (pin "4") (pinfunction "4_4") (pintype "passive"))
    )
    (net (code "57") (name "Net-(C2-Pad+)") (class "Default")
      (node (ref "C2") (pin "+") (pinfunction "+_+") (pintype "passive"))
      (node (ref "R5") (pin "2") (pinfunction "2_2") (pintype "passive"))
    )
    (net (code "58") (name "Net-(C5-Pad-)") (class "Default")
      (node (ref "C5") (pin "-") (pinfunction "-_-") (pintype "passive"))
      (node (ref "R17") (pin "1") (pinfunction "1_1") (pintype "passive"))
    )
    (net (code "59") (name "Net-(C6-Pad-)") (class "Default")
      (node (ref "C6") (pin "-") (pinfunction "-_-") (pintype "passive"))
      (node (ref "R14") (pin "2") (pinfunction "2_2") (pintype "passive"))
    )
    (net (code "60") (name "Net-(C7-Pad-)") (class "Default")
      (node (ref "C7") (pin "-") (pinfunction "-_-") (pintype "passive"))
      (node (ref "R48") (pin "1") (pinfunction "1_1") (pintype "passive"))
    )
    (net (code "61") (name "Net-(C8-Pad1)") (class "Default")
      (node (ref "C8") (pin "1") (pinfunction "1_1") (pintype "passive"))
      (node (ref "R21") (pin "1") (pinfunction "1_1") (pintype "passive"))
    )
    (net (code "62") (name "Net-(C17-Pad1)") (class "Default")
      (node (ref "C17") (pin "1") (pinfunction "1_1") (pintype "passive"))
      (node (ref "R22") (pin "1") (pinfunction "1_1") (pintype "passive"))
    )
    (net (code "63") (name "Net-(C30-Pad1)") (class "Default")
      (node (ref "C30") (pin "1") (pinfunction "1_1") (pintype "passive"))
      (node (ref "R57") (pin "1") (pinfunction "1_1") (pintype "passive"))
    )
    (net (code "64") (name "Net-(C35-Pad1)") (class "Default")
      (node (ref "C35") (pin "1") (pinfunction "1_1") (pintype "passive"))
      (node (ref "R55") (pin "1") (pinfunction "1_1") (pintype "passive"))
    )
    (net (code "65") (name "Net-(C51-Pad1)") (class "Default")
      (node (ref "C51") (pin "1") (pinfunction "1_1") (pintype "passive"))
      (node (ref "C56") (pin "+") (pinfunction "+_+") (pintype "passive"))
      (node (ref "C57") (pin "+") (pinfunction "+_+") (pintype "passive"))
      (node (ref "IC24") (pin "2") (pinfunction "2_2") (pintype "passive"))
    )
    (net (code "66") (name "Net-(C51-Pad2)") (class "Default")
      (node (ref "C51") (pin "2") (pinfunction "2_2") (pintype "passive"))
      (node (ref "IC24") (pin "7") (pinfunction "7_7") (pintype "passive"))
    )
    (net (code "67") (name "Net-(C56-Pad-)") (class "Default")
      (node (ref "C56") (pin "-") (pinfunction "-_-") (pintype "passive"))
      (node (ref "C57") (pin "-") (pinfunction "-_-") (pintype "passive"))
      (node (ref "IC24") (pin "4") (pinfunction "4_4") (pintype "passive"))
    )
    (net (code "68") (name "Net-(D3-PadC)") (class "Default")
      (node (ref "D3") (pin "C") (pinfunction "C_C") (pintype "passive"))
      (node (ref "D4") (pin "C") (pinfunction "C_C") (pintype "passive"))
    )
    (net (code "69") (name "Net-(D7-PadA)") (class "Default")
      (node (ref "D7") (pin "A") (pinfunction "A_A") (pintype "passive"))
      (node (ref "J8") (pin "+12V1") (pinfunction "1_+12V1") (pintype "passive"))
      (node (ref "J8") (pin "+12V2") (pinfunction "1_+12V2") (pintype "passive"))
    )
    (net (code "70") (name "Net-(D8-PadC)") (class "Default")
      (node (ref "D8") (pin "C") (pinfunction "C_C") (pintype "passive"))
      (node (ref "J8") (pin "-12V1") (pinfunction "5_-12V1") (pintype "passive"))
      (node (ref "J8") (pin "-12V2") (pinfunction "5_-12V2") (pintype "passive"))
    )
    (net (code "71") (name "Net-(IC2A--IN)") (class "Default")
      (node (ref "IC2") (pin "2") (pinfunction "-IN_2") (pintype "input"))
      (node (ref "R41") (pin "1") (pinfunction "1_1") (pintype "passive"))
      (node (ref "R42") (pin "2") (pinfunction "2_2") (pintype "passive"))
    )
    (net (code "72") (name "Net-(IC2B--IN)") (class "Default")
      (node (ref "IC2") (pin "6") (pinfunction "-IN_6") (pintype "input"))
      (node (ref "R7") (pin "2") (pinfunction "2_2") (pintype "passive"))
      (node (ref "R8") (pin "2") (pinfunction "2_2") (pintype "passive"))
    )
    (net (code "73") (name "Net-(IC3A--IN)") (class "Default")
      (node (ref "C25") (pin "1") (pinfunction "1_1") (pintype "passive"))
      (node (ref "IC3") (pin "2") (pinfunction "-IN_2") (pintype "input"))
      (node (ref "R43") (pin "2") (pinfunction "2_2") (pintype "passive"))
      (node (ref "R44") (pin "2") (pinfunction "2_2") (pintype "passive"))
      (node (ref "R45") (pin "1") (pinfunction "1_1") (pintype "passive"))
    )
    (net (code "74") (name "Net-(IC3A-OUT)") (class "Default")
      (node (ref "C25") (pin "2") (pinfunction "2_2") (pintype "passive"))
      (node (ref "IC3") (pin "1") (pinfunction "OUT_1") (pintype "output"))
      (node (ref "Q2") (pin "2") (pinfunction "B_2") (pintype "passive"))
    )
    (net (code "75") (name "Net-(IC3B--IN)") (class "Default")
      (node (ref "C12") (pin "1") (pinfunction "1_1") (pintype "passive"))
      (node (ref "IC3") (pin "6") (pinfunction "-IN_6") (pintype "input"))
      (node (ref "IC4") (pin "12") (pinfunction "OUT_12") (pintype "output"))
      (node (ref "R11") (pin "2") (pinfunction "2_2") (pintype "passive"))
      (node (ref "R12") (pin "1") (pinfunction "1_1") (pintype "passive"))
    )
    (net (code "76") (name "Net-(IC3B-OUT)") (class "Default")
      (node (ref "C12") (pin "2") (pinfunction "2_2") (pintype "passive"))
      (node (ref "IC3") (pin "7") (pinfunction "OUT_7") (pintype "output"))
      (node (ref "R10") (pin "2") (pinfunction "2_2") (pintype "passive"))
      (node (ref "R11") (pin "1") (pinfunction "1_1") (pintype "passive"))
    )
    (net (code "77") (name "Net-(IC4A-B)") (class "Default")
      (node (ref "IC4") (pin "5") (pinfunction "OUT_5") (pintype "output"))
      (node (ref "IC4") (pin "7") (pinfunction "B_7") (pintype "passive"))
      (node (ref "R49") (pin "2") (pinfunction "2_2") (pintype "passive"))
    )
    (net (code "78") (name "Net-(IC4C-IN_P)") (class "Default")
      (node (ref "IC4") (pin "3") (pinfunction "IN_P_3") (pintype "input"))
      (node (ref "R47") (pin "1") (pinfunction "1_1") (pintype "passive"))
      (node (ref "R48") (pin "2") (pinfunction "2_2") (pintype "passive"))
    )
    (net (code "79") (name "Net-(IC4C-I_BIAS)") (class "Default")
      (node (ref "IC4") (pin "1") (pinfunction "I_BIAS_1") (pintype "input"))
      (node (ref "R46") (pin "1") (pinfunction "1_1") (pintype "passive"))
    )
    (net (code "80") (name "Net-(IC4D-IN_P)") (class "Default")
      (node (ref "IC4") (pin "14") (pinfunction "IN_P_14") (pintype "input"))
      (node (ref "R13") (pin "2") (pinfunction "2_2") (pintype "passive"))
      (node (ref "R14") (pin "1") (pinfunction "1_1") (pintype "passive"))
    )
    (net (code "81") (name "Net-(IC4D-I_BIAS)") (class "Default")
      (node (ref "IC4") (pin "16") (pinfunction "I_BIAS_16") (pintype "input"))
      (node (ref "Q2") (pin "1") (pinfunction "C_1") (pintype "passive"))
    )
    (net (code "82") (name "Net-(IC5A--IN)") (class "Default")
      (node (ref "C28") (pin "1") (pinfunction "1_1") (pintype "passive"))
      (node (ref "IC5") (pin "2") (pinfunction "-IN_2") (pintype "input"))
      (node (ref "IC6") (pin "4") (pinfunction "OUT_4") (pintype "output"))
    )
    (net (code "83") (name "Net-(IC5B--IN)") (class "Default")
      (node (ref "IC5") (pin "6") (pinfunction "-IN_6") (pintype "input"))
      (node (ref "R52") (pin "2") (pinfunction "2_2") (pintype "passive"))
      (node (ref "R53") (pin "1") (pinfunction "1_1") (pintype "passive"))
    )
    (net (code "84") (name "Net-(IC5B-OUT)") (class "Default")
      (node (ref "IC5") (pin "7") (pinfunction "OUT_7") (pintype "output"))
      (node (ref "R18") (pin "2") (pinfunction "2_2") (pintype "passive"))
      (node (ref "R53") (pin "2") (pinfunction "2_2") (pintype "passive"))
    )
    (net (code "85") (name "Net-(IC5C--IN)") (class "Default")
      (node (ref "IC5") (pin "9") (pinfunction "-IN_9") (pintype "input"))
      (node (ref "R15") (pin "2") (pinfunction "2_2") (pintype "passive"))
      (node (ref "R16") (pin "1") (pinfunction "1_1") (pintype "passive"))
      (node (ref "R17") (pin "2") (pinfunction "2_2") (pintype "passive"))
      (node (ref "R18") (pin "1") (pinfunction "1_1") (pintype "passive"))
      (node (ref "R19") (pin "1") (pinfunction "1_1") (pintype "passive"))
    )
    (net (code "86") (name "Net-(IC5D--IN)") (class "Default")
      (node (ref "C14") (pin "1") (pinfunction "1_1") (pintype "passive"))
      (node (ref "D4") (pin "A") (pinfunction "A_A") (pintype "passive"))
      (node (ref "IC5") (pin "13") (pinfunction "-IN_13") (pintype "input"))
      (node (ref "IC6") (pin "13") (pinfunction "OUT_13") (pintype "output"))
    )
    (net (code "87") (name "Net-(IC6A-IN)") (class "Default")
      (node (ref "IC6") (pin "2") (pinfunction "IN_2") (pintype "input"))
      (node (ref "R54") (pin "2") (pinfunction "2_2") (pintype "passive"))
      (node (ref "R55") (pin "2") (pinfunction "2_2") (pintype "passive"))
    )
    (net (code "88") (name "Net-(IC6B-CTRL)") (class "Default")
      (node (ref "IC6") (pin "6") (pinfunction "CTRL_6") (pintype "input"))
      (node (ref "R56") (pin "2") (pinfunction "2_2") (pintype "passive"))
    )
    (net (code "89") (name "Net-(IC6B-IN)") (class "Default")
      (node (ref "IC6") (pin "7") (pinfunction "IN_7") (pintype "input"))
      (node (ref "R57") (pin "2") (pinfunction "2_2") (pintype "passive"))
      (node (ref "R58") (pin "2") (pinfunction "2_2") (pintype "passive"))
      (node (ref "R59") (pin "2") (pinfunction "2_2") (pintype "passive"))
      (node (ref "R60") (pin "2") (pinfunction "2_2") (pintype "passive"))
    )
    (net (code "90") (name "Net-(IC6B-OUT)") (class "Default")
      (node (ref "IC6") (pin "5") (pinfunction "OUT_5") (pintype "output"))
      (node (ref "IC7") (pin "2") (pinfunction "-IN_2") (pintype "input"))
      (node (ref "R61") (pin "1") (pinfunction "1_1") (pintype "passive"))
    )
    (net (code "91") (name "Net-(IC6C-CTRL)") (class "Default")
      (node (ref "IC6") (pin "11") (pinfunction "CTRL_11") (pintype "input"))
      (node (ref "IC7") (pin "1") (pinfunction "OUT_1") (pintype "output"))
      (node (ref "R75") (pin "1") (pinfunction "E_1") (pintype "passive"))
      (node (ref "R75") (pin "2") (pinfunction "S_2") (pintype "passive"))
    )
    (net (code "92") (name "Net-(IC6C-IN)") (class "Default")
      (node (ref "IC6") (pin "10") (pinfunction "IN_10") (pintype "input"))
      (node (ref "R22") (pin "2") (pinfunction "2_2") (pintype "passive"))
      (node (ref "R23") (pin "2") (pinfunction "2_2") (pintype "passive"))
      (node (ref "R24") (pin "2") (pinfunction "2_2") (pintype "passive"))
    )
    (net (code "93") (name "Net-(IC6C-OUT)") (class "Default")
      (node (ref "C9") (pin "1") (pinfunction "1_1") (pintype "passive"))
      (node (ref "IC6") (pin "12") (pinfunction "OUT_12") (pintype "output"))
      (node (ref "IC7") (pin "6") (pinfunction "-IN_6") (pintype "input"))
      (node (ref "Q1") (pin "2") (pinfunction "S_2") (pintype "passive"))
    )
    (net (code "94") (name "Net-(IC6D-IN)") (class "Default")
      (node (ref "IC6") (pin "15") (pinfunction "IN_15") (pintype "input"))
      (node (ref "R20") (pin "2") (pinfunction "2_2") (pintype "passive"))
      (node (ref "R21") (pin "2") (pinfunction "2_2") (pintype "passive"))
    )
    (net (code "95") (name "Net-(IC8-+IN)") (class "Default")
      (node (ref "C20") (pin "1") (pinfunction "1_1") (pintype "passive"))
      (node (ref "IC8") (pin "2") (pinfunction "+IN_2") (pintype "input"))
      (node (ref "R26") (pin "2") (pinfunction "2_2") (pintype "passive"))
    )
    (net (code "96") (name "Net-(IC8--IN)") (class "Default")
      (node (ref "C32") (pin "1") (pinfunction "1_1") (pintype "passive"))
      (node (ref "IC8") (pin "3") (pinfunction "-IN_3") (pintype "input"))
      (node (ref "R63") (pin "1") (pinfunction "1_1") (pintype "passive"))
      (node (ref "R64") (pin "2") (pinfunction "2_2") (pintype "passive"))
    )
    (net (code "97") (name "Net-(IC8-OUT)") (class "Default")
      (node (ref "C20") (pin "2") (pinfunction "2_2") (pintype "passive"))
      (node (ref "IC8") (pin "7") (pinfunction "OUT_7") (pintype "output"))
      (node (ref "R27") (pin "1") (pinfunction "1_1") (pintype "passive"))
      (node (ref "R6") (pin "1") (pinfunction "1_1") (pintype "passive"))
    )
    (net (code "98") (name "Net-(IC9A--IN)") (class "Default")
      (node (ref "D6") (pin "A") (pinfunction "A_A") (pintype "passive"))
      (node (ref "IC9") (pin "2") (pinfunction "-IN_2") (pintype "input"))
      (node (ref "R65") (pin "2") (pinfunction "2_2") (pintype "passive"))
      (node (ref "R66") (pin "2") (pinfunction "2_2") (pintype "passive"))
      (node (ref "R67") (pin "1") (pinfunction "1_1") (pintype "passive"))
      (node (ref "R68") (pin "2") (pinfunction "2_2") (pintype "passive"))
      (node (ref "R69") (pin "2") (pinfunction "2_2") (pintype "passive"))
    )
    (net (code "99") (name "Net-(IC9A-OUT)") (class "Default")
      (node (ref "D5") (pin "A") (pinfunction "A_A") (pintype "passive"))
      (node (ref "D6") (pin "C") (pinfunction "C_C") (pintype "passive"))
      (node (ref "IC9") (pin "1") (pinfunction "OUT_1") (pintype "output"))
    )
    (net (code "100") (name "Net-(IC9B--IN)") (class "Default")
      (node (ref "IC9") (pin "6") (pinfunction "-IN_6") (pintype "input"))
      (node (ref "R28") (pin "2") (pinfunction "2_2") (pintype "passive"))
      (node (ref "R29") (pin "1") (pinfunction "1_1") (pintype "passive"))
      (node (ref "R30") (pin "2") (pinfunction "2_2") (pintype "passive"))
    )
    (net (code "101") (name "Net-(IC10A--IN)") (class "Default")
      (node (ref "IC10") (pin "2") (pinfunction "-IN_2") (pintype "input"))
      (node (ref "R70") (pin "2") (pinfunction "2_2") (pintype "passive"))
      (node (ref "R71") (pin "2") (pinfunction "2_2") (pintype "passive"))
      (node (ref "R72") (pin "1") (pinfunction "1_1") (pintype "passive"))
    )
    (net (code "102") (name "Net-(IC10B-+IN)") (class "Default")
      (node (ref "IC10") (pin "5") (pinfunction "+IN_5") (pintype "input"))
      (node (ref "R73") (pin "2") (pinfunction "2_2") (pintype "passive"))
    )
    (net (code "103") (name "Net-(IC10B--IN)") (class "Default")
      (node (ref "IC10") (pin "6") (pinfunction "-IN_6") (pintype "input"))
      (node (ref "IC9") (pin "7") (pinfunction "OUT_7") (pintype "output"))
      (node (ref "R29") (pin "2") (pinfunction "2_2") (pintype "passive"))
    )
    (net (code "104") (name "Net-(IC10C--IN)") (class "Default")
      (node (ref "IC10") (pin "9") (pinfunction "-IN_9") (pintype "input"))
      (node (ref "R36") (pin "2") (pinfunction "2_2") (pintype "passive"))
      (node (ref "R37") (pin "1") (pinfunction "1_1") (pintype "passive"))
      (node (ref "R40") (pin "2") (pinfunction "2_2") (pintype "passive"))
    )
    (net (code "105") (name "Net-(IC10D--IN)") (class "Default")
      (node (ref "IC10") (pin "13") (pinfunction "-IN_13") (pintype "input"))
      (node (ref "R31") (pin "1") (pinfunction "1_1") (pintype "passive"))
      (node (ref "R32") (pin "2") (pinfunction "2_2") (pintype "passive"))
      (node (ref "R33") (pin "2") (pinfunction "2_2") (pintype "passive"))
      (node (ref "R34") (pin "2") (pinfunction "2_2") (pintype "passive"))
      (node (ref "R35") (pin "2") (pinfunction "2_2") (pintype "passive"))
    )
    (net (code "106") (name "Net-(IC15B-O)") (class "Default")
      (node (ref "IC15") (pin "4") (pinfunction "O_4") (pintype "output"))
      (node (ref "IC22") (pin "5") (pinfunction "G_5") (pintype "input"))
    )
    (net (code "107") (name "Net-(IC15C-O)") (class "Default")
      (node (ref "IC15") (pin "6") (pinfunction "O_6") (pintype "output"))
      (node (ref "IC22") (pin "6") (pinfunction "H_6") (pintype "input"))
    )
    (net (code "108") (name "Net-(IC15E-I)") (class "Default")
      (node (ref "IC15") (pin "11") (pinfunction "I_11") (pintype "input"))
      (node (ref "IC16") (pin "6") (pinfunction "QG_6") (pintype "tri_state"))
    )
    (net (code "109") (name "Net-(IC15F-I)") (class "Default")
      (node (ref "IC15") (pin "14") (pinfunction "I_14") (pintype "input"))
      (node (ref "IC16") (pin "7") (pinfunction "QH_7") (pintype "tri_state"))
    )
    (net (code "110") (name "Net-(IC23-PB6(XTAL1{slash}TOSC1))") (class "Default")
      (node (ref "C54") (pin "2") (pinfunction "2_2") (pintype "passive"))
      (node (ref "IC23") (pin "9") (pinfunction "PB6(XTAL1/TOSC1)_9") (pintype "bidirectional"))
      (node (ref "Q3") (pin "2") (pinfunction "2_2") (pintype "passive"))
    )
    (net (code "111") (name "Net-(IC23-PB7(XTAL2{slash}TOSC2))") (class "Default")
      (node (ref "C55") (pin "2") (pinfunction "2_2") (pintype "passive"))
      (node (ref "IC23") (pin "10") (pinfunction "PB7(XTAL2/TOSC2)_10") (pintype "bidirectional"))
      (node (ref "Q3") (pin "1") (pinfunction "1_1") (pintype "passive"))
    )
    (net (code "112") (name "Net-(J3-PadT)") (class "Default")
      (node (ref "J3") (pin "T") (pinfunction "T_T") (pintype "passive"))
      (node (ref "R35") (pin "1") (pinfunction "1_1") (pintype "passive"))
    )
    (net (code "113") (name "Net-(OK1-A)") (class "Default")
      (node (ref "D1") (pin "C") (pinfunction "C_C") (pintype "passive"))
      (node (ref "OK1") (pin "2") (pinfunction "A_2") (pintype "passive"))
      (node (ref "R1") (pin "2") (pinfunction "2_2") (pintype "passive"))
    )
    (net (code "114") (name "Net-(OK1-C)") (class "Default")
      (node (ref "D1") (pin "A") (pinfunction "A_A") (pintype "passive"))
      (node (ref "OK1") (pin "3") (pinfunction "C_3") (pintype "passive"))
      (node (ref "X1") (pin "5") (pinfunction "5_5") (pintype "passive"))
    )
    (net (code "115") (name "Net-(Q1-D)") (class "Default")
      (node (ref "C9") (pin "2") (pinfunction "2_2") (pintype "passive"))
      (node (ref "C9") (pin "3") (pinfunction "3_3") (pintype "passive"))
      (node (ref "Q1") (pin "3") (pinfunction "D_3") (pintype "passive"))
      (node (ref "R25") (pin "2") (pinfunction "2_2") (pintype "passive"))
    )
    (net (code "116") (name "Net-(Q1-G)") (class "Default")
      (node (ref "Q1") (pin "1") (pinfunction "G_1") (pintype "passive"))
      (node (ref "R6") (pin "2") (pinfunction "2_2") (pintype "passive"))
    )
    (net (code "117") (name "Net-(Q2-E)") (class "Default")
      (node (ref "Q2") (pin "3") (pinfunction "E_3") (pintype "passive"))
      (node (ref "R45") (pin "2") (pinfunction "2_2") (pintype "passive"))
    )
    (net (code "118") (name "Net-(R1-Pad1)") (class "Default")
      (node (ref "R1") (pin "1") (pinfunction "1_1") (pintype "passive"))
      (node (ref "X1") (pin "4") (pinfunction "4_4") (pintype "passive"))
    )
    (net (code "119") (name "Net-(R3-Pad1)") (class "Default")
      (node (ref "R3") (pin "1") (pinfunction "1_1") (pintype "passive"))
      (node (ref "X2") (pin "4") (pinfunction "4_4") (pintype "passive"))
    )
    (net (code "120") (name "Net-(R4-Pad2)") (class "Default")
      (node (ref "R4") (pin "2") (pinfunction "2_2") (pintype "passive"))
      (node (ref "X2") (pin "5") (pinfunction "5_5") (pintype "passive"))
    )
    (net (code "121") (name "Net-(R74-E)") (class "Default")
      (node (ref "R59") (pin "1") (pinfunction "1_1") (pintype "passive"))
      (node (ref "R74") (pin "1") (pinfunction "E_1") (pintype "passive"))
      (node (ref "R74") (pin "2") (pinfunction "S_2") (pintype "passive"))
    )
    (net (code "122") (name "Net-(R75-A)") (class "Default")
      (node (ref "R61") (pin "2") (pinfunction "2_2") (pintype "passive"))
      (node (ref "R75") (pin "3") (pinfunction "A_3") (pintype "passive"))
    )
    (net (code "123") (name "Net-(R76-A)") (class "Default")
      (node (ref "R67") (pin "2") (pinfunction "2_2") (pintype "passive"))
      (node (ref "R76") (pin "3") (pinfunction "A_3") (pintype "passive"))
    )
    (net (code "124") (name "Net-(S1A-O)") (class "Default")
      (node (ref "D2") (pin "A") (pinfunction "A_A") (pintype "passive"))
      (node (ref "S1") (pin "1") (pinfunction "O_1") (pintype "passive"))
    )
    (net (code "125") (name "Net-(S1A-P)") (class "Default")
      (node (ref "J1") (pin "3") (pinfunction "3_3") (pintype "passive"))
      (node (ref "S1") (pin "2") (pinfunction "P_2") (pintype "passive"))
    )
    (net (code "126") (name "PITCH_MOD") (class "Default")
      (node (ref "IC18") (pin "12") (pinfunction "X3_12") (pintype "bidirectional"))
      (node (ref "J5") (pin "3") (pinfunction "3_3") (pintype "passive"))
    )
    (net (code "127") (name "POT1") (class "Default")
      (node (ref "IC17") (pin "12") (pinfunction "X3_12") (pintype "bidirectional"))
      (node (ref "J5") (pin "9") (pinfunction "9_9") (pintype "passive"))
    )
    (net (code "128") (name "POT2") (class "Default")
      (node (ref "IC17") (pin "13") (pinfunction "X0_13") (pintype "bidirectional"))
      (node (ref "J5") (pin "10") (pinfunction "10_10") (pintype "passive"))
    )
    (net (code "129") (name "POT3") (class "Default")
      (node (ref "IC17") (pin "14") (pinfunction "X1_14") (pintype "bidirectional"))
      (node (ref "J5") (pin "11") (pinfunction "11_11") (pintype "passive"))
    )
    (net (code "130") (name "POT4") (class "Default")
      (node (ref "IC17") (pin "15") (pinfunction "X2_15") (pintype "bidirectional"))
      (node (ref "J5") (pin "12") (pinfunction "12_12") (pintype "passive"))
    )
    (net (code "131") (name "POT5") (class "Default")
      (node (ref "IC17") (pin "1") (pinfunction "X4_1") (pintype "bidirectional"))
      (node (ref "J5") (pin "13") (pinfunction "13_13") (pintype "passive"))
    )
    (net (code "132") (name "POT6") (class "Default")
      (node (ref "IC17") (pin "2") (pinfunction "X6_2") (pintype "bidirectional"))
      (node (ref "J5") (pin "14") (pinfunction "14_14") (pintype "passive"))
    )
    (net (code "133") (name "POT7") (class "Default")
      (node (ref "IC17") (pin "4") (pinfunction "X7_4") (pintype "bidirectional"))
      (node (ref "J5") (pin "15") (pinfunction "15_15") (pintype "passive"))
    )
    (net (code "134") (name "POT8") (class "Default")
      (node (ref "IC17") (pin "5") (pinfunction "X5_5") (pintype "bidirectional"))
      (node (ref "J5") (pin "16") (pinfunction "16_16") (pintype "passive"))
    )
    (net (code "135") (name "POT9") (class "Default")
      (node (ref "IC18") (pin "1") (pinfunction "X4_1") (pintype "bidirectional"))
      (node (ref "J5") (pin "8") (pinfunction "8_8") (pintype "passive"))
    )
    (net (code "136") (name "POT10") (class "Default")
      (node (ref "IC18") (pin "2") (pinfunction "X6_2") (pintype "bidirectional"))
      (node (ref "J5") (pin "7") (pinfunction "7_7") (pintype "passive"))
    )
    (net (code "137") (name "PWM_OUT") (class "Default")
      (node (ref "C2") (pin "-") (pinfunction "-_-") (pintype "passive"))
      (node (ref "IC23") (pin "5") (pinfunction "PD3(INT1)_5") (pintype "bidirectional"))
    )
    (net (code "138") (name "PW_MOD") (class "Default")
      (node (ref "IC18") (pin "15") (pinfunction "X2_15") (pintype "bidirectional"))
      (node (ref "J5") (pin "6") (pinfunction "6_6") (pintype "passive"))
    )
    (net (code "139") (name "PW_POT") (class "Default")
      (node (ref "J6") (pin "7") (pinfunction "7_7") (pintype "passive"))
      (node (ref "R30") (pin "1") (pinfunction "1_1") (pintype "passive"))
    )
    (net (code "140") (name "REF_-4.096") (class "Default")
      (node (ref "C37") (pin "1") (pinfunction "1_1") (pintype "passive"))
      (node (ref "IC13") (pin "3") (pinfunction "A_3") (pintype "passive"))
      (node (ref "R62") (pin "2") (pinfunction "2_2") (pintype "passive"))
      (node (ref "R66") (pin "1") (pinfunction "1_1") (pintype "passive"))
      (node (ref "R74") (pin "3") (pinfunction "A_3") (pintype "passive"))
    )
    (net (code "141") (name "REF_4.096_CV_OUT") (class "Default")
      (node (ref "C10") (pin "1") (pinfunction "1_1") (pintype "passive"))
      (node (ref "IC1") (pin "2") (pinfunction "C_2") (pintype "passive"))
      (node (ref "R42") (pin "1") (pinfunction "1_1") (pintype "passive"))
      (node (ref "R8") (pin "1") (pinfunction "1_1") (pintype "passive"))
      (node (ref "R9") (pin "1") (pinfunction "1_1") (pintype "passive"))
    )
    (net (code "142") (name "REF_4.096_TC") (class "Default")
      (node (ref "C36") (pin "1") (pinfunction "1_1") (pintype "passive"))
      (node (ref "IC12") (pin "2") (pinfunction "C_2") (pintype "passive"))
      (node (ref "R51") (pin "1") (pinfunction "1_1") (pintype "passive"))
      (node (ref "R56") (pin "1") (pinfunction "1_1") (pintype "passive"))
    )
    (net (code "143") (name "RES_IN") (class "Default")
      (node (ref "J7") (pin "3") (pinfunction "3_3") (pintype "passive"))
      (node (ref "R52") (pin "1") (pinfunction "1_1") (pintype "passive"))
    )
    (net (code "144") (name "RST") (class "Default")
      (node (ref "IC23") (pin "1") (pinfunction "PC6(/RESET)_1") (pintype "bidirectional"))
      (node (ref "ISP") (pin "5") (pinfunction "5_5") (pintype "passive"))
      (node (ref "R77") (pin "1") (pinfunction "1_1") (pintype "passive"))
    )
    (net (code "145") (name "SAW_INV") (class "Default")
      (node (ref "IC10") (pin "1") (pinfunction "OUT_1") (pintype "output"))
      (node (ref "IC11") (pin "1") (pinfunction "CLK_1") (pintype "input"))
      (node (ref "R39") (pin "1") (pinfunction "1_1") (pintype "passive"))
      (node (ref "R72") (pin "2") (pinfunction "2_2") (pintype "passive"))
      (node (ref "R73") (pin "1") (pinfunction "1_1") (pintype "passive"))
    )
    (net (code "146") (name "SCK") (class "Default")
      (node (ref "IC19") (pin "3") (pinfunction "SCK_3") (pintype "input"))
      (node (ref "IC20") (pin "3") (pinfunction "SCK_3") (pintype "input"))
      (node (ref "IC23") (pin "19") (pinfunction "PB5(SCK)_19") (pintype "bidirectional"))
      (node (ref "ISP") (pin "3") (pinfunction "3_3") (pintype "passive"))
    )
    (net (code "147") (name "SQUARE") (class "Default")
      (node (ref "IC10") (pin "7") (pinfunction "OUT_7") (pintype "output"))
      (node (ref "R38") (pin "1") (pinfunction "1_1") (pintype "passive"))
      (node (ref "R40") (pin "1") (pinfunction "1_1") (pintype "passive"))
    )
    (net (code "148") (name "SS_DAC1") (class "Default")
      (node (ref "IC20") (pin "2") (pinfunction "#CS_2") (pintype "input"))
      (node (ref "IC23") (pin "15") (pinfunction "PB1(OC1A)_15") (pintype "bidirectional"))
    )
    (net (code "149") (name "SS_DAC2") (class "Default")
      (node (ref "IC19") (pin "2") (pinfunction "#CS_2") (pintype "input"))
      (node (ref "IC23") (pin "13") (pinfunction "PD7(AIN1)_13") (pintype "bidirectional"))
    )
    (net (code "150") (name "SUB") (class "Default")
      (node (ref "J6") (pin "1") (pinfunction "1_1") (pintype "passive"))
      (node (ref "R34") (pin "1") (pinfunction "1_1") (pintype "passive"))
    )
    (net (code "151") (name "V+") (class "Default")
      (node (ref "C38") (pin "+") (pinfunction "+_+") (pintype "passive"))
      (node (ref "D2") (pin "C") (pinfunction "C_C") (pintype "passive"))
      (node (ref "D7") (pin "C") (pinfunction "C_C") (pintype "passive"))
      (node (ref "IC14") (pin "IN") (pinfunction "IN_IN") (pintype "input"))
      (node (ref "IC24") (pin "8") (pinfunction "8_8") (pintype "passive"))
    )
    (net (code "152") (name "V-") (class "Default")
      (node (ref "C52") (pin "-") (pinfunction "-_-") (pintype "passive"))
      (node (ref "D8") (pin "A") (pinfunction "A_A") (pintype "passive"))
      (node (ref "IC21") (pin "IN") (pinfunction "IN_IN") (pintype "input"))
      (node (ref "IC24") (pin "5") (pinfunction "5_5") (pintype "passive"))
    )
    (net (code "153") (name "VCA_CV_IN") (class "Default")
      (node (ref "J7") (pin "11") (pinfunction "11_11") (pintype "passive"))
      (node (ref "R44") (pin "1") (pinfunction "1_1") (pintype "passive"))
    )
    (net (code "154") (name "VCA_IN") (class "Default")
      (node (ref "C6") (pin "+") (pinfunction "+_+") (pintype "passive"))
      (node (ref "J7") (pin "9") (pinfunction "9_9") (pintype "passive"))
    )
    (net (code "155") (name "VCC") (class "Default")
      (node (ref "C1") (pin "1") (pinfunction "1_1") (pintype "passive"))
      (node (ref "C11") (pin "1") (pinfunction "1_1") (pintype "passive"))
      (node (ref "C13") (pin "1") (pinfunction "1_1") (pintype "passive"))
      (node (ref "C16") (pin "1") (pinfunction "1_1") (pintype "passive"))
      (node (ref "C19") (pin "1") (pinfunction "1_1") (pintype "passive"))
      (node (ref "C21") (pin "1") (pinfunction "1_1") (pintype "passive"))
      (node (ref "C23") (pin "1") (pinfunction "1_1") (pintype "passive"))
      (node (ref "C29") (pin "1") (pinfunction "1_1") (pintype "passive"))
      (node (ref "C34") (pin "1") (pinfunction "1_1") (pintype "passive"))
      (node (ref "C39") (pin "1") (pinfunction "1_1") (pintype "passive"))
      (node (ref "C40") (pin "1") (pinfunction "1_1") (pintype "passive"))
      (node (ref "C41") (pin "1") (pinfunction "1_1") (pintype "passive"))
      (node (ref "C42") (pin "1") (pinfunction "1_1") (pintype "passive"))
      (node (ref "C43") (pin "1") (pinfunction "1_1") (pintype "passive"))
      (node (ref "C44") (pin "+") (pinfunction "+_+") (pintype "passive"))
      (node (ref "C46") (pin "1") (pinfunction "1_1") (pintype "passive"))
      (node (ref "C47") (pin "1") (pinfunction "1_1") (pintype "passive"))
      (node (ref "C50") (pin "1") (pinfunction "1_1") (pintype "passive"))
      (node (ref "C53") (pin "1") (pinfunction "1_1") (pintype "passive"))
      (node (ref "IC10") (pin "4") (pinfunction "V+_4") (pintype "power_in"))
      (node (ref "IC11") (pin "14") (pinfunction "VDD_14") (pintype "power_in"))
      (node (ref "IC14") (pin "OUT") (pinfunction "OUT_OUT") (pintype "passive"))
      (node (ref "IC15") (pin "1") (pinfunction "VDD_1") (pintype "power_in"))
      (node (ref "IC16") (pin "10") (pinfunction "SCL_10") (pintype "input"))
      (node (ref "IC16") (pin "16") (pinfunction "VCC_16") (pintype "power_in"))
      (node (ref "IC17") (pin "16") (pinfunction "VCC_16") (pintype "power_in"))
      (node (ref "IC18") (pin "16") (pinfunction "VCC_16") (pintype "power_in"))
      (node (ref "IC19") (pin "1") (pinfunction "VDD_1") (pintype "power_in"))
      (node (ref "IC2") (pin "8") (pinfunction "V+_8") (pintype "power_in"))
      (node (ref "IC20") (pin "1") (pinfunction "VDD_1") (pintype "power_in"))
      (node (ref "IC22") (pin "16") (pinfunction "VCC_16") (pintype "power_in"))
      (node (ref "IC23") (pin "20") (pinfunction "AVCC_20") (pintype "power_in"))
      (node (ref "IC23") (pin "7") (pinfunction "VCC_7") (pintype "power_in"))
      (node (ref "IC3") (pin "8") (pinfunction "V+_8") (pintype "power_in"))
      (node (ref "IC4") (pin "11") (pinfunction "V+_11") (pintype "power_in"))
      (node (ref "IC5") (pin "4") (pinfunction "V+_4") (pintype "power_in"))
      (node (ref "IC6") (pin "16") (pinfunction "V+_16") (pintype "power_in"))
      (node (ref "IC7") (pin "8") (pinfunction "V+_8") (pintype "power_in"))
      (node (ref "IC8") (pin "5") (pinfunction "ON_5") (pintype "passive"))
      (node (ref "IC8") (pin "6") (pinfunction "ON/STR_6") (pintype "passive"))
      (node (ref "IC8") (pin "8") (pinfunction "V+_8") (pintype "power_in"))
      (node (ref "IC9") (pin "8") (pinfunction "V+_8") (pintype "power_in"))
      (node (ref "ISP") (pin "2") (pinfunction "2_2") (pintype "passive"))
      (node (ref "J5") (pin "1") (pinfunction "1_1") (pintype "passive"))
      (node (ref "J6") (pin "16") (pinfunction "16_16") (pintype "passive"))
      (node (ref "JP4") (pin "5") (pinfunction "5_5") (pintype "passive"))
      (node (ref "OK1") (pin "8") (pinfunction "VCC_8") (pintype "passive"))
      (node (ref "R2") (pin "2") (pinfunction "2_2") (pintype "passive"))
      (node (ref "R27") (pin "2") (pinfunction "2_2") (pintype "passive"))
      (node (ref "R3") (pin "2") (pinfunction "2_2") (pintype "passive"))
      (node (ref "R51") (pin "2") (pinfunction "2_2") (pintype "passive"))
      (node (ref "R63") (pin "2") (pinfunction "2_2") (pintype "passive"))
      (node (ref "R77") (pin "2") (pinfunction "2_2") (pintype "passive"))
      (node (ref "R9") (pin "2") (pinfunction "2_2") (pintype "passive"))
      (node (ref "RN1") (pin "1") (pinfunction "1_1") (pintype "passive"))
    )
    (net (code "156") (name "VCF_CV_IN") (class "Default")
      (node (ref "J6") (pin "9") (pinfunction "9_9") (pintype "passive"))
      (node (ref "R69") (pin "1") (pinfunction "1_1") (pintype "passive"))
    )
    (net (code "157") (name "VCF_CV_OUT") (class "Default")
      (node (ref "IC2") (pin "7") (pinfunction "OUT_7") (pintype "output"))
      (node (ref "J7") (pin "15") (pinfunction "15_15") (pintype "passive"))
      (node (ref "R7") (pin "1") (pinfunction "1_1") (pintype "passive"))
    )
    (net (code "158") (name "VCF_OUT") (class "Default")
      (node (ref "C7") (pin "+") (pinfunction "+_+") (pintype "passive"))
      (node (ref "J7") (pin "6") (pinfunction "6_6") (pintype "passive"))
    )
    (net (code "159") (name "VCF_OVERDRIVE") (class "Default")
      (node (ref "IC4") (pin "8") (pinfunction "E_8") (pintype "passive"))
      (node (ref "J7") (pin "12") (pinfunction "12_12") (pintype "passive"))
      (node (ref "R50") (pin "2") (pinfunction "2_2") (pintype "passive"))
    )
    (net (code "160") (name "VCO_CV_IN") (class "Default")
      (node (ref "J6") (pin "6") (pinfunction "6_6") (pintype "passive"))
      (node (ref "R58") (pin "1") (pinfunction "1_1") (pintype "passive"))
    )
    (net (code "161") (name "VCO_CV_OUT") (class "Default")
      (node (ref "IC2") (pin "1") (pinfunction "OUT_1") (pintype "output"))
      (node (ref "J7") (pin "16") (pinfunction "16_16") (pintype "passive"))
      (node (ref "R41") (pin "2") (pinfunction "2_2") (pintype "passive"))
    )
    (net (code "162") (name "VCO_SAW_CORE") (class "Default")
      (node (ref "IC7") (pin "7") (pinfunction "OUT_7") (pintype "output"))
      (node (ref "R25") (pin "1") (pinfunction "1_1") (pintype "passive"))
      (node (ref "R26") (pin "1") (pinfunction "1_1") (pintype "passive"))
      (node (ref "R70") (pin "1") (pinfunction "1_1") (pintype "passive"))
    )
    (net (code "163") (name "VCO_SYNC") (class "Default")
      (node (ref "C32") (pin "2") (pinfunction "2_2") (pintype "passive"))
      (node (ref "J6") (pin "13") (pinfunction "13_13") (pintype "passive"))
    )
    (net (code "164") (name "VCO_TUNING_FB") (class "Default")
      (node (ref "IC10") (pin "8") (pinfunction "OUT_8") (pintype "output"))
      (node (ref "IC23") (pin "14") (pinfunction "PB0(ICP)_14") (pintype "bidirectional"))
      (node (ref "R37") (pin "2") (pinfunction "2_2") (pintype "passive"))
    )
    (net (code "165") (name "VEE") (class "Default")
      (node (ref "C15") (pin "2") (pinfunction "2_2") (pintype "passive"))
      (node (ref "C18") (pin "2") (pinfunction "2_2") (pintype "passive"))
      (node (ref "C22") (pin "2") (pinfunction "2_2") (pintype "passive"))
      (node (ref "C24") (pin "2") (pinfunction "2_2") (pintype "passive"))
      (node (ref "C26") (pin "2") (pinfunction "2_2") (pintype "passive"))
      (node (ref "C27") (pin "2") (pinfunction "2_2") (pintype "passive"))
      (node (ref "C31") (pin "2") (pinfunction "2_2") (pintype "passive"))
      (node (ref "C33") (pin "2") (pinfunction "2_2") (pintype "passive"))
      (node (ref "C48") (pin "2") (pinfunction "2_2") (pintype "passive"))
      (node (ref "C49") (pin "-") (pinfunction "-_-") (pintype "passive"))
      (node (ref "IC10") (pin "11") (pinfunction "V-_11") (pintype "power_in"))
      (node (ref "IC11") (pin "2") (pinfunction "RES_2") (pintype "input"))
      (node (ref "IC11") (pin "7") (pinfunction "VSS_7") (pintype "power_in"))
      (node (ref "IC2") (pin "4") (pinfunction "V-_4") (pintype "power_in"))
      (node (ref "IC21") (pin "OUT") (pinfunction "OUT_OUT") (pintype "passive"))
      (node (ref "IC3") (pin "4") (pinfunction "V-_4") (pintype "power_in"))
      (node (ref "IC4") (pin "6") (pinfunction "V-_6") (pintype "power_in"))
      (node (ref "IC5") (pin "11") (pinfunction "V-_11") (pintype "power_in"))
      (node (ref "IC6") (pin "9") (pinfunction "V-_9") (pintype "power_in"))
      (node (ref "IC7") (pin "4") (pinfunction "V-_4") (pintype "power_in"))
      (node (ref "IC8") (pin "1") (pinfunction "GND_1") (pintype "passive"))
      (node (ref "IC8") (pin "4") (pinfunction "V-_4") (pintype "power_in"))
      (node (ref "IC9") (pin "4") (pinfunction "V-_4") (pintype "power_in"))
      (node (ref "J6") (pin "12") (pinfunction "12_12") (pintype "passive"))
      (node (ref "R23") (pin "1") (pinfunction "1_1") (pintype "passive"))
      (node (ref "R36") (pin "1") (pinfunction "1_1") (pintype "passive"))
      (node (ref "R50") (pin "1") (pinfunction "1_1") (pintype "passive"))
      (node (ref "R62") (pin "1") (pinfunction "1_1") (pintype "passive"))
      (node (ref "R71") (pin "1") (pinfunction "1_1") (pintype "passive"))
    )
    (net (code "166") (name "VOL_IN") (class "Default")
      (node (ref "J7") (pin "13") (pinfunction "13_13") (pintype "passive"))
      (node (ref "R10") (pin "1") (pinfunction "1_1") (pintype "passive"))
    )
    (net (code "167") (name "VOL_OUT") (class "Default")
      (node (ref "J2") (pin "T") (pinfunction "T_T") (pintype "passive"))
      (node (ref "J7") (pin "14") (pinfunction "14_14") (pintype "passive"))
    )
    (net (code "168") (name "unconnected-(IC4C-I_DIODE-Pad2)") (class "Default")
      (node (ref "IC4") (pin "2") (pinfunction "I_DIODE_2") (pintype "input"))
    )
    (net (code "169") (name "unconnected-(IC4D-I_DIODE-Pad15)") (class "Default")
      (node (ref "IC4") (pin "15") (pinfunction "I_DIODE_15") (pintype "input"))
    )
    (net (code "170") (name "unconnected-(IC6E-MODE-Pad1)") (class "Default")
      (node (ref "IC6") (pin "1") (pinfunction "MODE_1") (pintype "input"))
    )
    (net (code "171") (name "unconnected-(IC11A-Q3-Pad9)") (class "Default")
      (node (ref "IC11") (pin "9") (pinfunction "Q3_9") (pintype "output"))
    )
    (net (code "172") (name "unconnected-(IC11A-Q4-Pad6)") (class "Default")
      (node (ref "IC11") (pin "6") (pinfunction "Q4_6") (pintype "output"))
    )
    (net (code "173") (name "unconnected-(IC11A-Q5-Pad5)") (class "Default")
      (node (ref "IC11") (pin "5") (pinfunction "Q5_5") (pintype "output"))
    )
    (net (code "174") (name "unconnected-(IC11A-Q6-Pad4)") (class "Default")
      (node (ref "IC11") (pin "4") (pinfunction "Q6_4") (pintype "output"))
    )
    (net (code "175") (name "unconnected-(IC11A-Q7-Pad3)") (class "Default")
      (node (ref "IC11") (pin "3") (pinfunction "Q7_3") (pintype "output"))
    )
    (net (code "176") (name "unconnected-(IC15A-O-Pad2)") (class "Default")
      (node (ref "IC15") (pin "2") (pinfunction "O_2") (pintype "output"))
    )
    (net (code "177") (name "unconnected-(IC15D-O-Pad10)") (class "Default")
      (node (ref "IC15") (pin "10") (pinfunction "O_10") (pintype "output"))
    )
    (net (code "178") (name "unconnected-(IC18A-X5-Pad5)") (class "Default")
      (node (ref "IC18") (pin "5") (pinfunction "X5_5") (pintype "bidirectional"))
    )
    (net (code "179") (name "unconnected-(IC18A-X7-Pad4)") (class "Default")
      (node (ref "IC18") (pin "4") (pinfunction "X7_4") (pintype "bidirectional"))
    )
    (net (code "180") (name "unconnected-(IC22A-~{QH}-Pad7)") (class "Default")
      (node (ref "IC22") (pin "7") (pinfunction "~{QH}_7") (pintype "output"))
    )
    (net (code "181") (name "unconnected-(IC24-Pad1)") (class "Default")
      (node (ref "IC24") (pin "1") (pinfunction "1_1") (pintype "passive"))
    )
    (net (code "182") (name "unconnected-(IC24-Pad6)") (class "Default")
      (node (ref "IC24") (pin "6") (pinfunction "6_6") (pintype "passive"))
    )
    (net (code "183") (name "unconnected-(J1-Pad2)") (class "Default")
      (node (ref "J1") (pin "2") (pinfunction "2_2") (pintype "passive"))
    )
    (net (code "184") (name "unconnected-(J2-PadTN)") (class "Default")
      (node (ref "J2") (pin "TN") (pinfunction "TN_TN") (pintype "passive"))
    )
    (net (code "185") (name "unconnected-(OK1-VB-Pad7)") (class "Default")
      (node (ref "OK1") (pin "7") (pinfunction "VB_7") (pintype "passive"))
    )
    (net (code "186") (name "unconnected-(S1A-S-Pad3)") (class "Default")
      (node (ref "S1") (pin "3") (pinfunction "S_3") (pintype "passive"))
    )
    (net (code "187") (name "unconnected-(X1-Pad1)") (class "Default")
      (node (ref "X1") (pin "1") (pinfunction "1_1") (pintype "passive"))
    )
    (net (code "188") (name "unconnected-(X1-Pad2)") (class "Default")
      (node (ref "X1") (pin "2") (pinfunction "2_2") (pintype "passive"))
    )
    (net (code "189") (name "unconnected-(X1-Pad3)") (class "Default")
      (node (ref "X1") (pin "3") (pinfunction "3_3") (pintype "passive"))
    )
    (net (code "190") (name "unconnected-(X2-Pad1)") (class "Default")
      (node (ref "X2") (pin "1") (pinfunction "1_1") (pintype "passive"))
    )
    (net (code "191") (name "unconnected-(X2-Pad3)") (class "Default")
      (node (ref "X2") (pin "3") (pinfunction "3_3") (pintype "passive"))
    )
  )
)
